# main_V3_0.net
KiCad netlist of a schematic drawn in EAGLE
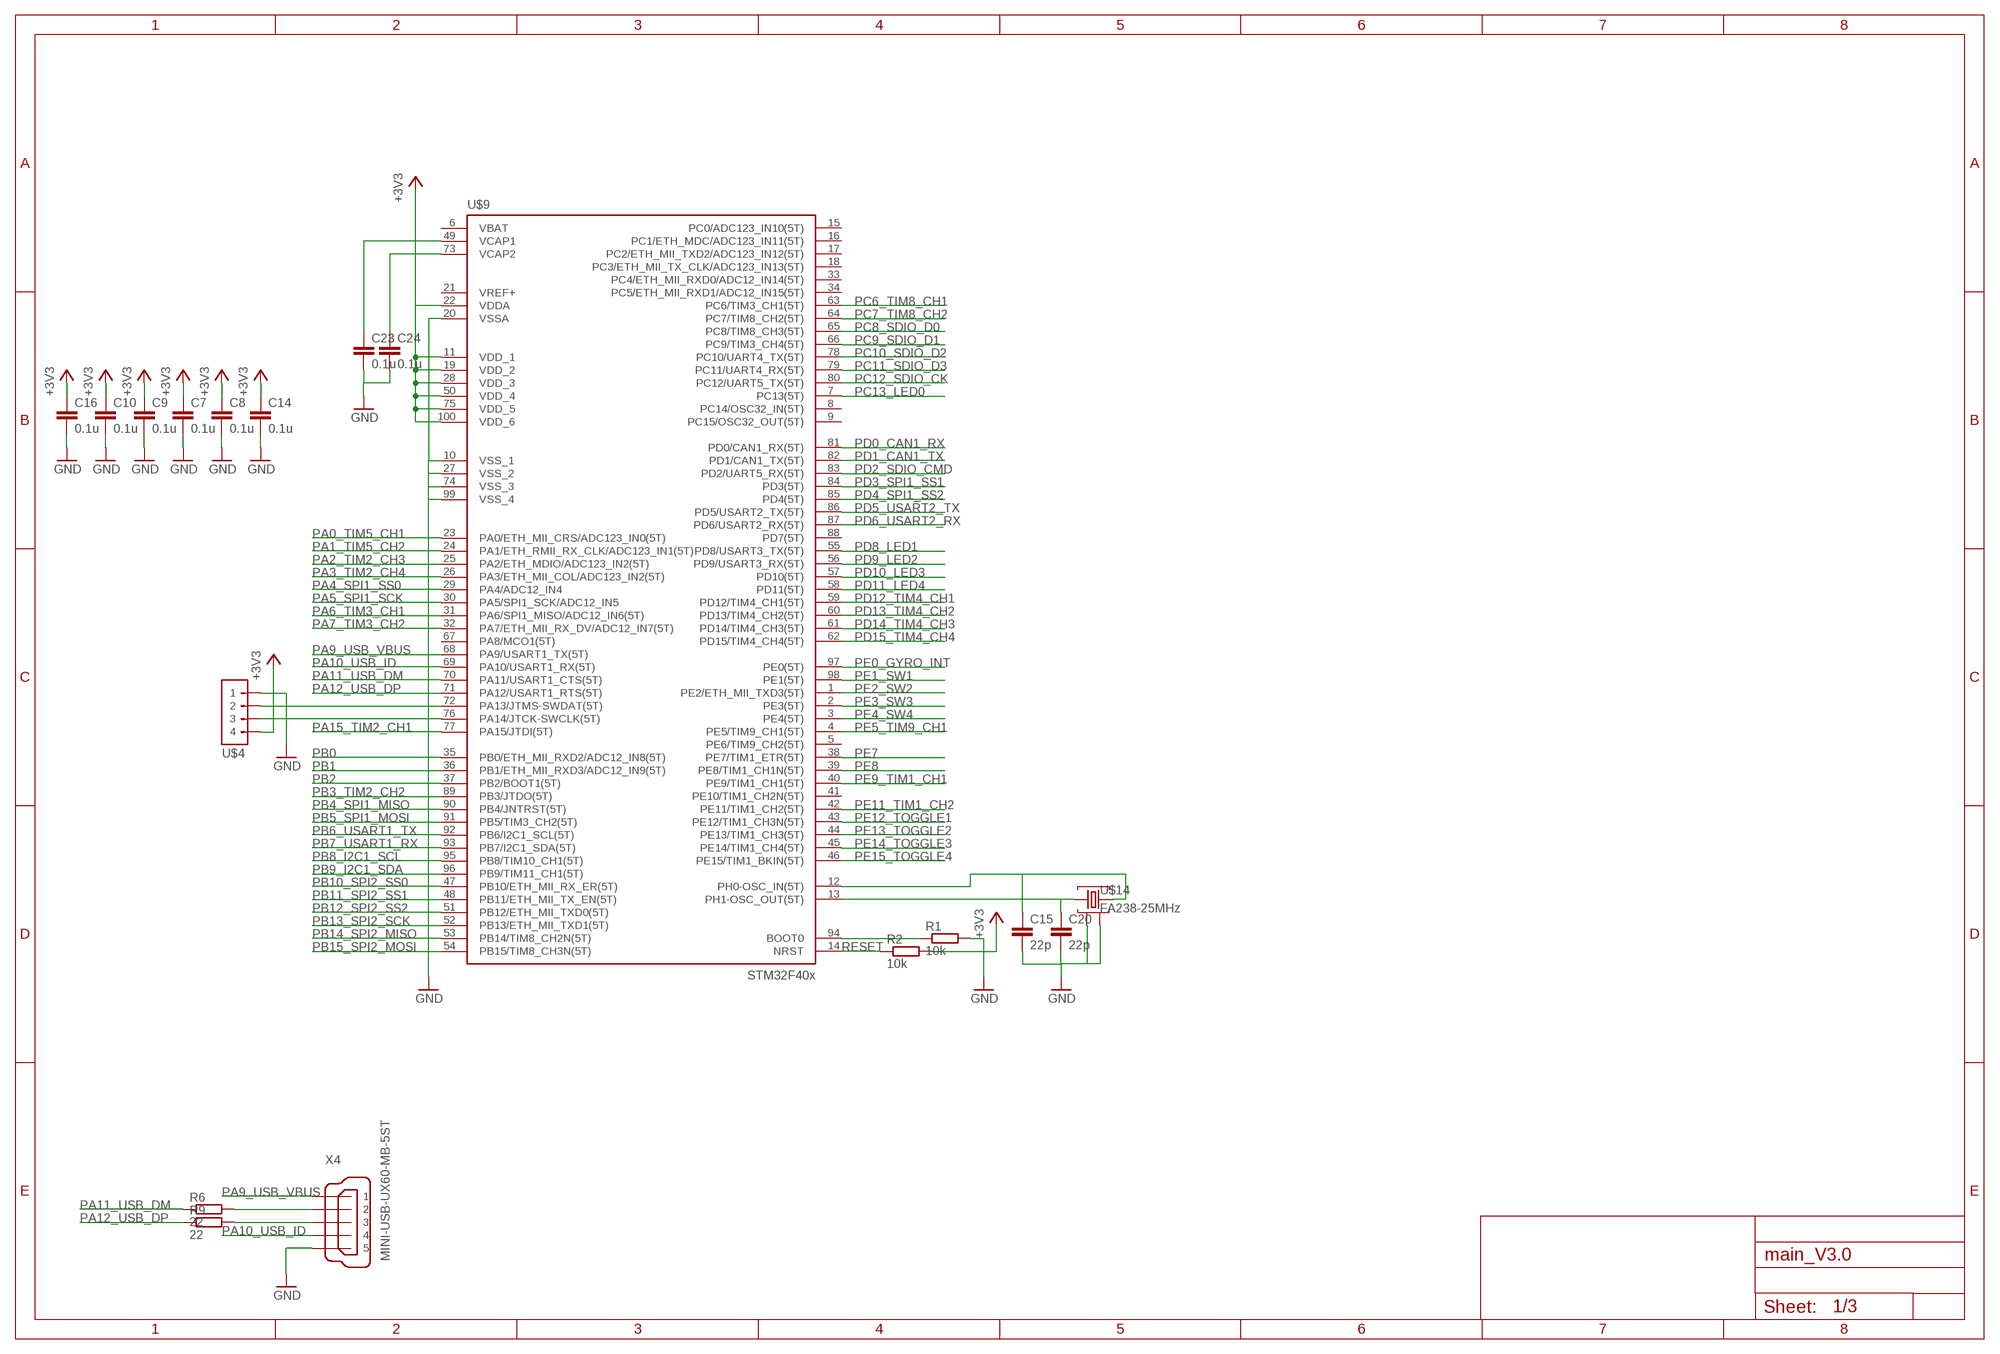
[diagram p0: schematic, sheet 1]
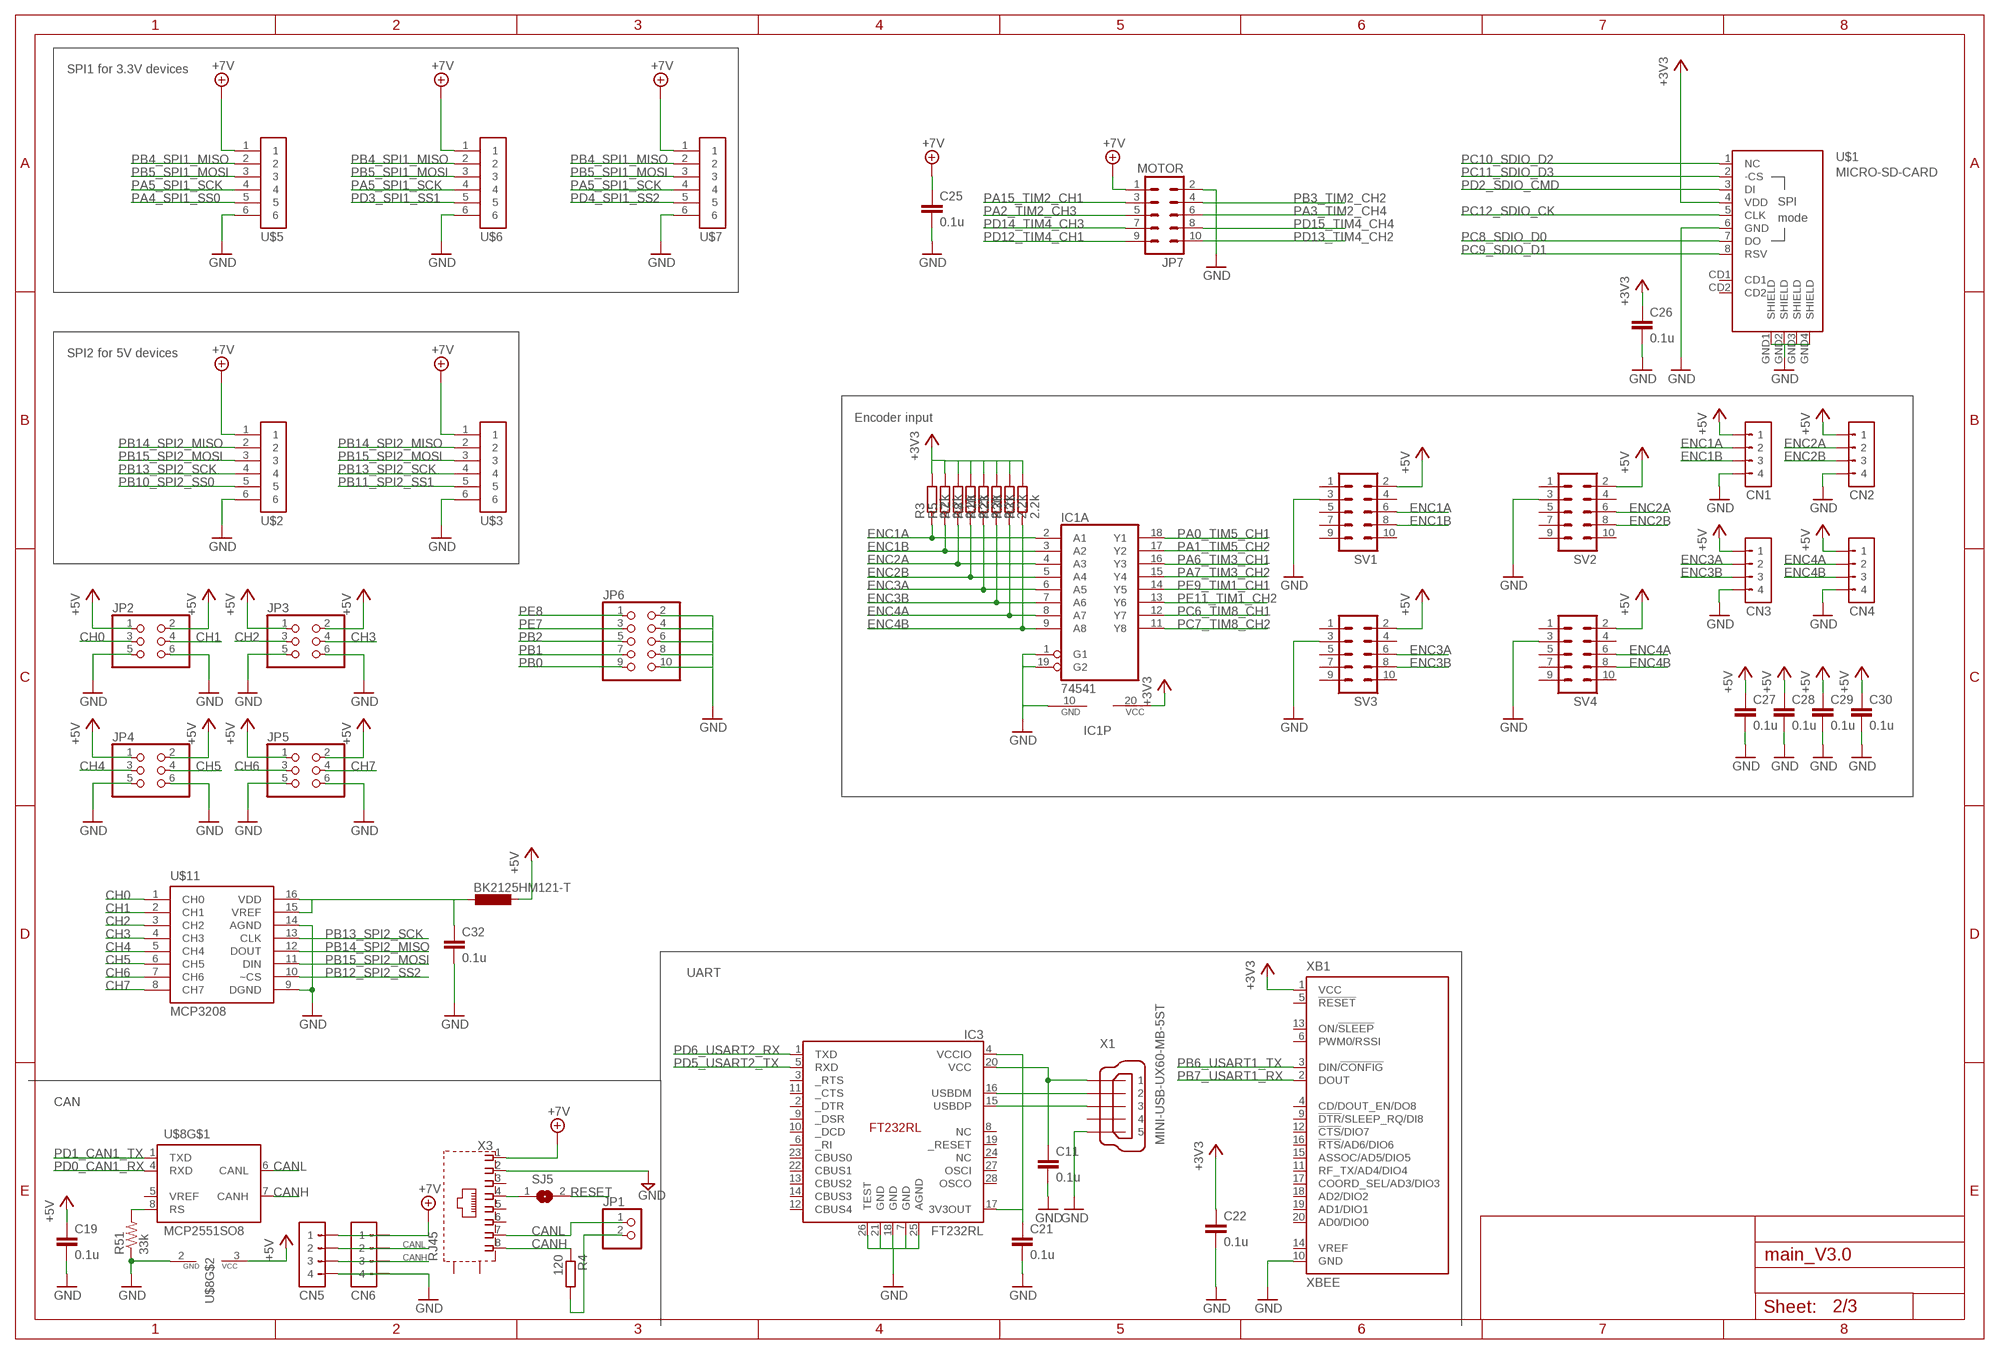
[diagram p1: schematic, sheet 2]
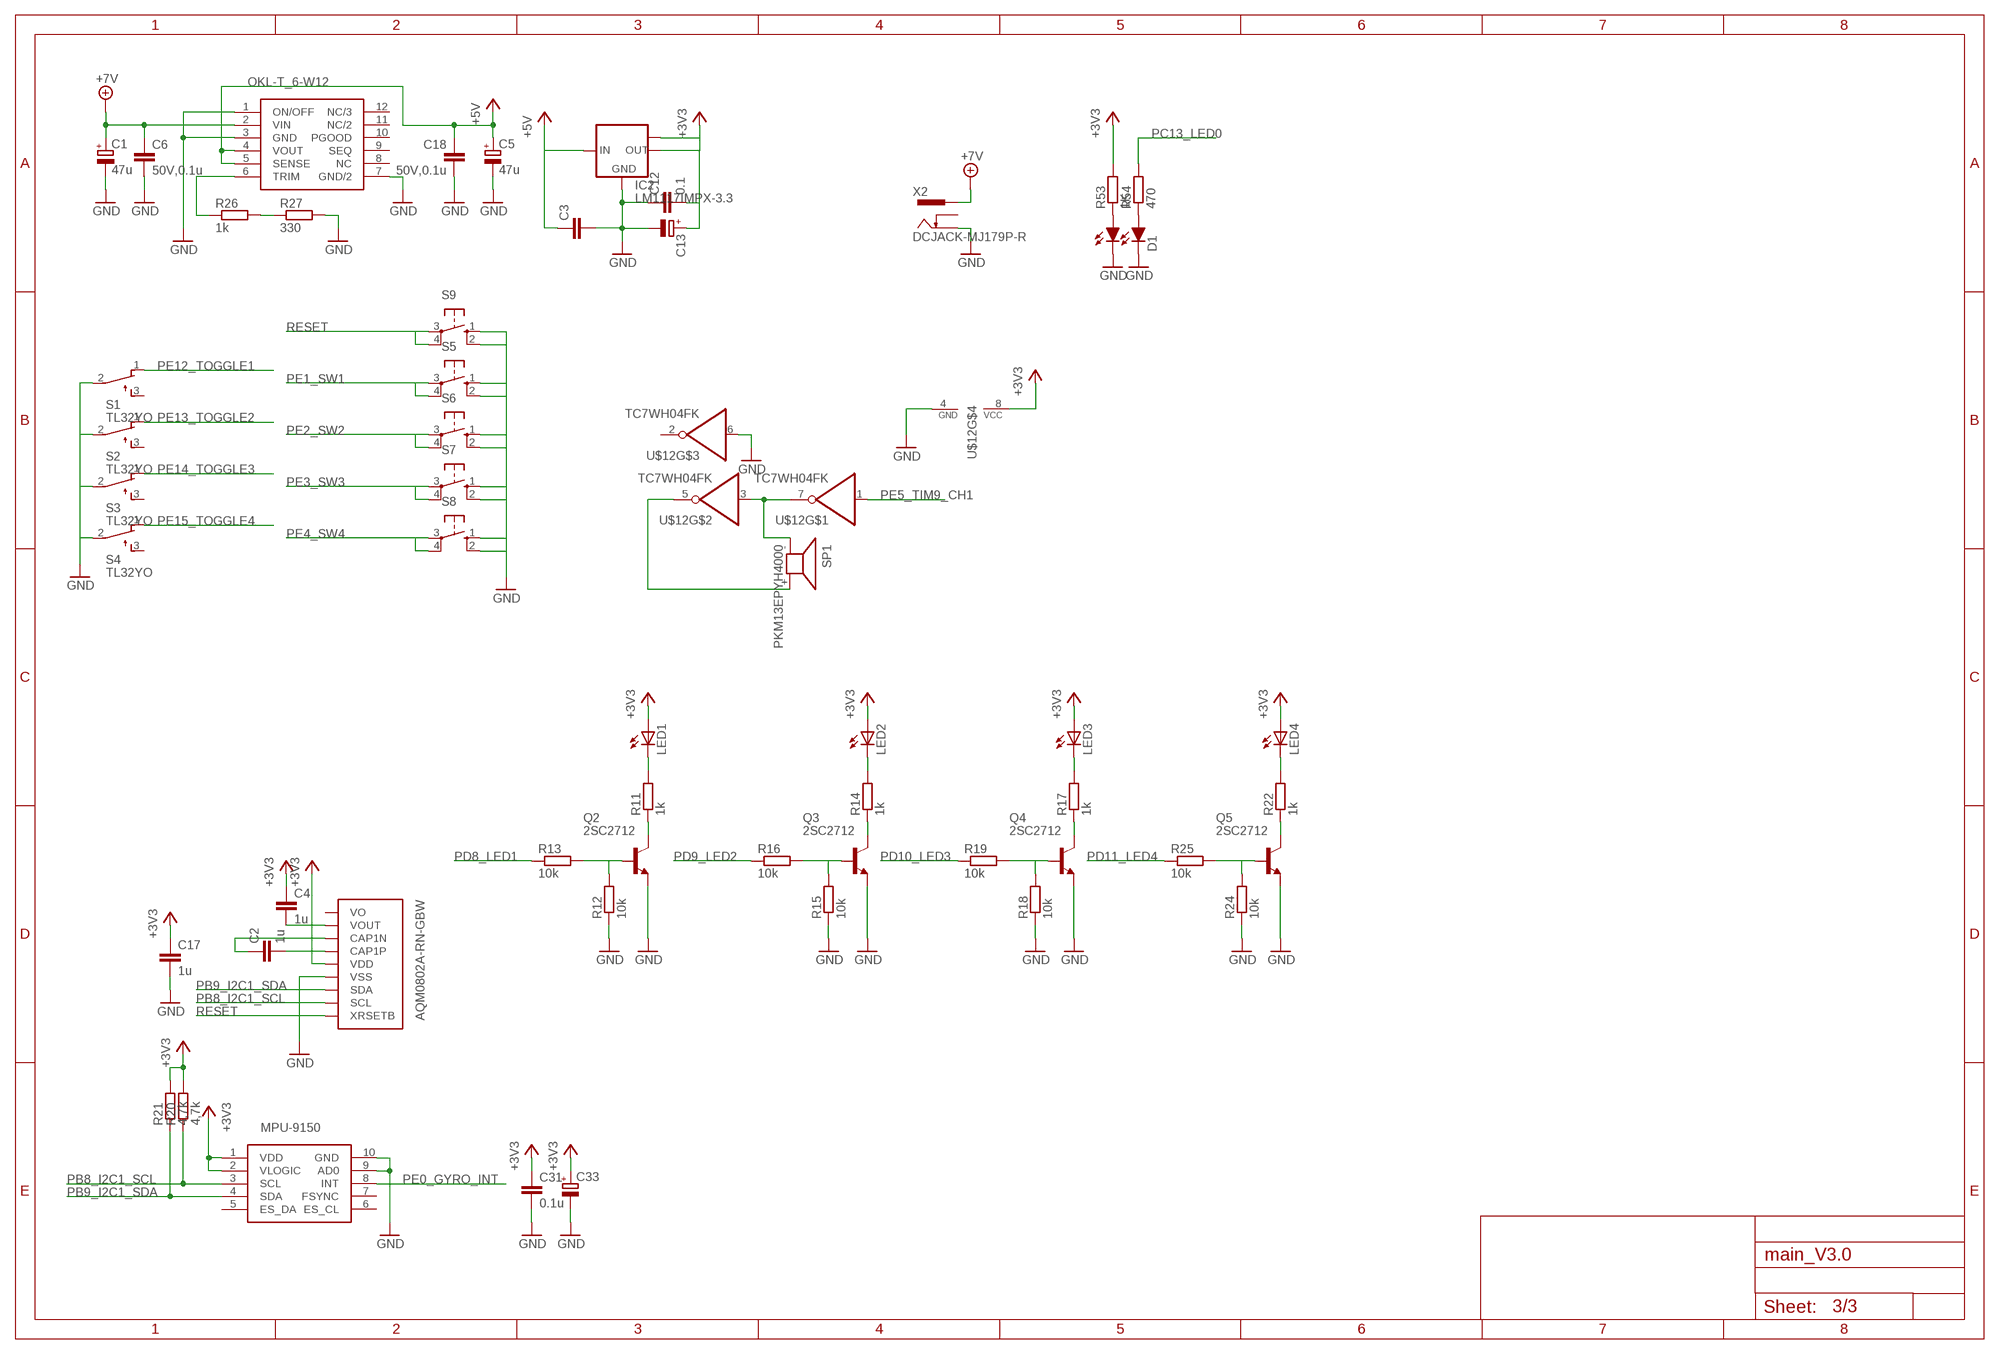
[diagram p2: schematic, sheet 3]

(export (version "E")
  (design (tool "Eeschema 10.0.6"))
  (components
    (comp (ref "AQM0802A-RN-GBW")
      (value "AQM0802A-RN-GBW")
      (footprint "eagle-import:AQM0802")
      (libsource (lib "eagle-import") (part "AQM0802A-RN-GBW"))
    )
    (comp (ref "C1")
      (value "47u")
      (footprint "eagle-import:153CLV-0405")
      (libsource (lib "eagle-import") (part "CPOL-EU153CLV-0405"))
    )
    (comp (ref "C2")
      (value "1u")
      (footprint "eagle-import:C0603K")
      (libsource (lib "eagle-import") (part "C-EUC0603K"))
    )
    (comp (ref "C3")
      (value "C-EUC0603")
      (footprint "eagle-import:C0603")
      (libsource (lib "eagle-import") (part "C-EUC0603"))
    )
    (comp (ref "C4")
      (value "1u")
      (footprint "eagle-import:C0603K")
      (libsource (lib "eagle-import") (part "C-EUC0603K"))
    )
    (comp (ref "C5")
      (value "47u")
      (footprint "eagle-import:153CLV-0405")
      (libsource (lib "eagle-import") (part "CPOL-EU153CLV-0405"))
    )
    (comp (ref "C6")
      (value "50V,0.1u")
      (footprint "eagle-import:C0603K")
      (libsource (lib "eagle-import") (part "C-EUC0603K"))
    )
    (comp (ref "C12")
      (value "0.1")
      (footprint "eagle-import:C0603")
      (libsource (lib "eagle-import") (part "C-EUC0603"))
    )
    (comp (ref "C13")
      (value "CPOL-EU153CLV-0505")
      (footprint "eagle-import:153CLV-0505")
      (libsource (lib "eagle-import") (part "CPOL-EU153CLV-0505"))
    )
    (comp (ref "C17")
      (value "1u")
      (footprint "eagle-import:C0603K")
      (libsource (lib "eagle-import") (part "C-EUC0603K"))
    )
    (comp (ref "C18")
      (value "50V,0.1u")
      (footprint "eagle-import:C0603K")
      (libsource (lib "eagle-import") (part "C-EUC0603K"))
    )
    (comp (ref "C31")
      (value "0.1u")
      (footprint "eagle-import:C0603K")
      (libsource (lib "eagle-import") (part "C-EUC0603K"))
    )
    (comp (ref "C33")
      (value "CPOL-EU153CLV-0505")
      (footprint "eagle-import:153CLV-0505")
      (libsource (lib "eagle-import") (part "CPOL-EU153CLV-0505"))
    )
    (comp (ref "D1")
      (value "SEC2XX4")
      (footprint "eagle-import:LED3025")
      (libsource (lib "eagle-import") (part "SEC2XX4"))
    )
    (comp (ref "IC2")
      (value "LM1117IMPX-3.3")
      (footprint "eagle-import:SOT223")
      (libsource (lib "eagle-import") (part "LM1117IMPX-3.3"))
    )
    (comp (ref "LED1")
      (value "LEDSML0603")
      (footprint "eagle-import:SML0603")
      (libsource (lib "eagle-import") (part "LEDSML0603"))
    )
    (comp (ref "LED2")
      (value "LEDSML0603")
      (footprint "eagle-import:SML0603")
      (libsource (lib "eagle-import") (part "LEDSML0603"))
    )
    (comp (ref "LED3")
      (value "LEDSML0603")
      (footprint "eagle-import:SML0603")
      (libsource (lib "eagle-import") (part "LEDSML0603"))
    )
    (comp (ref "LED4")
      (value "LEDSML0603")
      (footprint "eagle-import:SML0603")
      (libsource (lib "eagle-import") (part "LEDSML0603"))
    )
    (comp (ref "Q2")
      (value "2SC2712")
      (footprint "eagle-import:SC-59(TYPE1)")
      (libsource (lib "eagle-import") (part "2SC2712"))
    )
    (comp (ref "Q3")
      (value "2SC2712")
      (footprint "eagle-import:SC-59(TYPE1)")
      (libsource (lib "eagle-import") (part "2SC2712"))
    )
    (comp (ref "Q4")
      (value "2SC2712")
      (footprint "eagle-import:SC-59(TYPE1)")
      (libsource (lib "eagle-import") (part "2SC2712"))
    )
    (comp (ref "Q5")
      (value "2SC2712")
      (footprint "eagle-import:SC-59(TYPE1)")
      (libsource (lib "eagle-import") (part "2SC2712"))
    )
    (comp (ref "R11")
      (value "1k")
      (footprint "eagle-import:R0603")
      (libsource (lib "eagle-import") (part "R-EU_R0603"))
    )
    (comp (ref "R12")
      (value "10k")
      (footprint "eagle-import:R0603")
      (libsource (lib "eagle-import") (part "R-EU_R0603"))
    )
    (comp (ref "R13")
      (value "10k")
      (footprint "eagle-import:R0603")
      (libsource (lib "eagle-import") (part "R-EU_R0603"))
    )
    (comp (ref "R14")
      (value "1k")
      (footprint "eagle-import:R0603")
      (libsource (lib "eagle-import") (part "R-EU_R0603"))
    )
    (comp (ref "R15")
      (value "10k")
      (footprint "eagle-import:R0603")
      (libsource (lib "eagle-import") (part "R-EU_R0603"))
    )
    (comp (ref "R16")
      (value "10k")
      (footprint "eagle-import:R0603")
      (libsource (lib "eagle-import") (part "R-EU_R0603"))
    )
    (comp (ref "R17")
      (value "1k")
      (footprint "eagle-import:R0603")
      (libsource (lib "eagle-import") (part "R-EU_R0603"))
    )
    (comp (ref "R18")
      (value "10k")
      (footprint "eagle-import:R0603")
      (libsource (lib "eagle-import") (part "R-EU_R0603"))
    )
    (comp (ref "R19")
      (value "10k")
      (footprint "eagle-import:R0603")
      (libsource (lib "eagle-import") (part "R-EU_R0603"))
    )
    (comp (ref "R20")
      (value "4,7k")
      (footprint "eagle-import:R0603")
      (libsource (lib "eagle-import") (part "R-EU_R0603"))
    )
    (comp (ref "R21")
      (value "4,7k")
      (footprint "eagle-import:R0603")
      (libsource (lib "eagle-import") (part "R-EU_R0603"))
    )
    (comp (ref "R22")
      (value "1k")
      (footprint "eagle-import:R0603")
      (libsource (lib "eagle-import") (part "R-EU_R0603"))
    )
    (comp (ref "R24")
      (value "10k")
      (footprint "eagle-import:R0603")
      (libsource (lib "eagle-import") (part "R-EU_R0603"))
    )
    (comp (ref "R25")
      (value "10k")
      (footprint "eagle-import:R0603")
      (libsource (lib "eagle-import") (part "R-EU_R0603"))
    )
    (comp (ref "R26")
      (value "1k")
      (footprint "eagle-import:R0603")
      (libsource (lib "eagle-import") (part "R-EU_R0603"))
    )
    (comp (ref "R27")
      (value "330")
      (footprint "eagle-import:R0603")
      (libsource (lib "eagle-import") (part "R-EU_R0603"))
    )
    (comp (ref "R53")
      (value "1K")
      (footprint "eagle-import:R0603")
      (libsource (lib "eagle-import") (part "R-EU_R0603"))
    )
    (comp (ref "R54")
      (value "470")
      (footprint "eagle-import:R0603")
      (libsource (lib "eagle-import") (part "R-EU_R0603"))
    )
    (comp (ref "S1")
      (value "TL32YO")
      (footprint "eagle-import:TL3XYO")
      (libsource (lib "eagle-import") (part "TL32YO"))
    )
    (comp (ref "S2")
      (value "TL32YO")
      (footprint "eagle-import:TL3XYO")
      (libsource (lib "eagle-import") (part "TL32YO"))
    )
    (comp (ref "S3")
      (value "TL32YO")
      (footprint "eagle-import:TL3XYO")
      (libsource (lib "eagle-import") (part "TL32YO"))
    )
    (comp (ref "S4")
      (value "TL32YO")
      (footprint "eagle-import:TL3XYO")
      (libsource (lib "eagle-import") (part "TL32YO"))
    )
    (comp (ref "S5")
      (value "10-XX")
      (footprint "eagle-import:B3F-10XX")
      (fields (field (name "MPN") "B3F-1000"))
      (libsource (lib "eagle-import") (part "10-XX"))
    )
    (comp (ref "S6")
      (value "10-XX")
      (footprint "eagle-import:B3F-10XX")
      (fields (field (name "MPN") "B3F-1000"))
      (libsource (lib "eagle-import") (part "10-XX"))
    )
    (comp (ref "S7")
      (value "10-XX")
      (footprint "eagle-import:B3F-10XX")
      (fields (field (name "MPN") "B3F-1000"))
      (libsource (lib "eagle-import") (part "10-XX"))
    )
    (comp (ref "S8")
      (value "10-XX")
      (footprint "eagle-import:B3F-10XX")
      (fields (field (name "MPN") "B3F-1000"))
      (libsource (lib "eagle-import") (part "10-XX"))
    )
    (comp (ref "S9")
      (value "10-XX")
      (footprint "eagle-import:B3F-10XX")
      (fields (field (name "MPN") "B3F-1000"))
      (libsource (lib "eagle-import") (part "10-XX"))
    )
    (comp (ref "SP1")
      (value "PKM13EPYH4000")
      (footprint "eagle-import:AL11P")
      (libsource (lib "eagle-import") (part "AL11P"))
    )
    (comp (ref "U$10")
      (value "MPU-9150")
      (footprint "eagle-import:MPU-9150")
      (libsource (lib "eagle-import") (part "MPU-9150"))
    )
    (comp (ref "U$12")
      (value "TC7WH04FK")
      (footprint "eagle-import:SSOP08")
      (libsource (lib "eagle-import") (part "TC7WH04FK"))
    )
    (comp (ref "U$13")
      (value "OKL-T/6-W12N")
      (footprint "eagle-import:OKL-T_6-W12")
      (libsource (lib "eagle-import") (part "OKL-T/6-W12N"))
    )
    (comp (ref "X2")
      (value "DCJACK-MJ179P-R")
      (footprint "eagle-import:MJ-179P-R")
      (libsource (lib "eagle-import") (part "DCJACK-MJ179P-R"))
    )
    (comp (ref "BK2125HM121-T")
      (value "L-EUL2012C")
      (footprint "eagle-import:L2012C")
      (libsource (lib "eagle-import") (part "L-EUL2012C"))
    )
    (comp (ref "C11")
      (value "0.1u")
      (footprint "eagle-import:C0603K")
      (libsource (lib "eagle-import") (part "C-EUC0603K"))
    )
    (comp (ref "C19")
      (value "0.1u")
      (footprint "eagle-import:C0603K")
      (libsource (lib "eagle-import") (part "C-EUC0603K"))
    )
    (comp (ref "C21")
      (value "0.1u")
      (footprint "eagle-import:C0603K")
      (libsource (lib "eagle-import") (part "C-EUC0603K"))
    )
    (comp (ref "C22")
      (value "0.1u")
      (footprint "eagle-import:C0603K")
      (libsource (lib "eagle-import") (part "C-EUC0603K"))
    )
    (comp (ref "C25")
      (value "0.1u")
      (footprint "eagle-import:C0603K")
      (libsource (lib "eagle-import") (part "C-EUC0603K"))
    )
    (comp (ref "C26")
      (value "0.1u")
      (footprint "eagle-import:C0603K")
      (libsource (lib "eagle-import") (part "C-EUC0603K"))
    )
    (comp (ref "C27")
      (value "0.1u")
      (footprint "eagle-import:C0603K")
      (libsource (lib "eagle-import") (part "C-EUC0603K"))
    )
    (comp (ref "C28")
      (value "0.1u")
      (footprint "eagle-import:C0603K")
      (libsource (lib "eagle-import") (part "C-EUC0603K"))
    )
    (comp (ref "C29")
      (value "0.1u")
      (footprint "eagle-import:C0603K")
      (libsource (lib "eagle-import") (part "C-EUC0603K"))
    )
    (comp (ref "C30")
      (value "0.1u")
      (footprint "eagle-import:C0603K")
      (libsource (lib "eagle-import") (part "C-EUC0603K"))
    )
    (comp (ref "C32")
      (value "0.1u")
      (footprint "eagle-import:C0603K")
      (libsource (lib "eagle-import") (part "C-EUC0603K"))
    )
    (comp (ref "CN1")
      (value "CN4-JST-XH-TOP")
      (footprint "eagle-import:JST-B4B-XH-A")
      (libsource (lib "eagle-import") (part "CN4-JST-XH-TOP"))
    )
    (comp (ref "CN2")
      (value "CN4-JST-XH-TOP")
      (footprint "eagle-import:JST-B4B-XH-A")
      (libsource (lib "eagle-import") (part "CN4-JST-XH-TOP"))
    )
    (comp (ref "CN3")
      (value "CN4-JST-XH-TOP")
      (footprint "eagle-import:JST-B4B-XH-A")
      (libsource (lib "eagle-import") (part "CN4-JST-XH-TOP"))
    )
    (comp (ref "CN4")
      (value "CN4-JST-XH-TOP")
      (footprint "eagle-import:JST-B4B-XH-A")
      (libsource (lib "eagle-import") (part "CN4-JST-XH-TOP"))
    )
    (comp (ref "CN5")
      (value "CN4-JST-XH-TOP")
      (footprint "eagle-import:JST-B4B-XH-A")
      (libsource (lib "eagle-import") (part "CN4-JST-XH-TOP"))
    )
    (comp (ref "CN6")
      (value "CN4-JST-XH-TOP")
      (footprint "eagle-import:JST-B4B-XH-A")
      (libsource (lib "eagle-import") (part "CN4-JST-XH-TOP"))
    )
    (comp (ref "IC1")
      (value "74541")
      (footprint "eagle-import:SOP20")
      (libsource (lib "eagle-import") (part "74541"))
    )
    (comp (ref "IC3")
      (value "FT232RL")
      (footprint "eagle-import:SSOP-28")
      (libsource (lib "eagle-import") (part "FT232RL"))
    )
    (comp (ref "JP1")
      (value "PINHD-1X2")
      (footprint "eagle-import:1X02")
      (libsource (lib "eagle-import") (part "PINHD-1X2"))
    )
    (comp (ref "JP2")
      (value "PINHD-2X3/90")
      (footprint "eagle-import:2X03_90")
      (libsource (lib "eagle-import") (part "PINHD-2X3/90"))
    )
    (comp (ref "JP3")
      (value "PINHD-2X3/90")
      (footprint "eagle-import:2X03_90")
      (libsource (lib "eagle-import") (part "PINHD-2X3/90"))
    )
    (comp (ref "JP4")
      (value "PINHD-2X3/90")
      (footprint "eagle-import:2X03_90")
      (libsource (lib "eagle-import") (part "PINHD-2X3/90"))
    )
    (comp (ref "JP5")
      (value "PINHD-2X3/90")
      (footprint "eagle-import:2X03_90")
      (libsource (lib "eagle-import") (part "PINHD-2X3/90"))
    )
    (comp (ref "JP6")
      (value "PINHD-2X5/90")
      (footprint "eagle-import:2X05_90")
      (libsource (lib "eagle-import") (part "PINHD-2X5/90"))
    )
    (comp (ref "JP7")
      (value "MOTOR")
      (footprint "eagle-import:ML10L")
      (libsource (lib "eagle-import") (part "ML10L"))
    )
    (comp (ref "R3")
      (value "2.2k")
      (footprint "eagle-import:R0603")
      (libsource (lib "eagle-import") (part "R-EU_R0603"))
    )
    (comp (ref "R4")
      (value "120")
      (footprint "eagle-import:R0603")
      (libsource (lib "eagle-import") (part "R-EU_R0603"))
    )
    (comp (ref "R5")
      (value "2.2k")
      (footprint "eagle-import:R0603")
      (libsource (lib "eagle-import") (part "R-EU_R0603"))
    )
    (comp (ref "R7")
      (value "2.2k")
      (footprint "eagle-import:R0603")
      (libsource (lib "eagle-import") (part "R-EU_R0603"))
    )
    (comp (ref "R8")
      (value "2.2k")
      (footprint "eagle-import:R0603")
      (libsource (lib "eagle-import") (part "R-EU_R0603"))
    )
    (comp (ref "R10")
      (value "2.2k")
      (footprint "eagle-import:R0603")
      (libsource (lib "eagle-import") (part "R-EU_R0603"))
    )
    (comp (ref "R23")
      (value "2.2k")
      (footprint "eagle-import:R0603")
      (libsource (lib "eagle-import") (part "R-EU_R0603"))
    )
    (comp (ref "R30")
      (value "2.2k")
      (footprint "eagle-import:R0603")
      (libsource (lib "eagle-import") (part "R-EU_R0603"))
    )
    (comp (ref "R31")
      (value "2.2k")
      (footprint "eagle-import:R0603")
      (libsource (lib "eagle-import") (part "R-EU_R0603"))
    )
    (comp (ref "R51")
      (value "33k")
      (footprint "eagle-import:R0603")
      (libsource (lib "eagle-import") (part "R-US_R0603"))
    )
    (comp (ref "SJ5") (value "SJ") (footprint "eagle-import:SJ") (libsource (lib "eagle-import") (part "SJ")))
    (comp (ref "SV1")
      (value "ML10L")
      (footprint "eagle-import:ML10L")
      (libsource (lib "eagle-import") (part "con-ml_ML10L"))
    )
    (comp (ref "SV2")
      (value "ML10L")
      (footprint "eagle-import:ML10L")
      (libsource (lib "eagle-import") (part "con-ml_ML10L"))
    )
    (comp (ref "SV3")
      (value "ML10L")
      (footprint "eagle-import:ML10L")
      (libsource (lib "eagle-import") (part "con-ml_ML10L"))
    )
    (comp (ref "SV4")
      (value "ML10L")
      (footprint "eagle-import:ML10L")
      (libsource (lib "eagle-import") (part "con-ml_ML10L"))
    )
    (comp (ref "U$1")
      (value "MICRO-SD-CARD")
      (footprint "eagle-import:DM3AT-SF-PEJ")
      (libsource (lib "eagle-import") (part "MICRO-SD-CARD"))
    )
    (comp (ref "U$2")
      (value "CN6")
      (footprint "eagle-import:JST-B6B-XH-A")
      (libsource (lib "eagle-import") (part "CN6"))
    )
    (comp (ref "U$3")
      (value "CN6")
      (footprint "eagle-import:JST-B6B-XH-A")
      (libsource (lib "eagle-import") (part "CN6"))
    )
    (comp (ref "U$5")
      (value "CN6")
      (footprint "eagle-import:JST-B6B-XH-A")
      (libsource (lib "eagle-import") (part "CN6"))
    )
    (comp (ref "U$6")
      (value "CN6")
      (footprint "eagle-import:JST-B6B-XH-A")
      (libsource (lib "eagle-import") (part "CN6"))
    )
    (comp (ref "U$7")
      (value "CN6")
      (footprint "eagle-import:JST-B6B-XH-A")
      (libsource (lib "eagle-import") (part "CN6"))
    )
    (comp (ref "U$8")
      (value "MCP2551SO8")
      (footprint "eagle-import:SO08")
      (libsource (lib "eagle-import") (part "MCP2551SO8"))
    )
    (comp (ref "U$11")
      (value "MCP3208")
      (footprint "eagle-import:SO16")
      (libsource (lib "eagle-import") (part "MCP3208"))
    )
    (comp (ref "X1")
      (value "MINI-USB-UX60-MB-5ST")
      (footprint "eagle-import:UX60-MB-5ST")
      (libsource (lib "eagle-import") (part "MINI-USB-UX60-MB-5ST"))
    )
    (comp (ref "X3")
      (value "RJ45")
      (footprint "eagle-import:LAN")
      (libsource (lib "eagle-import") (part "RJ45"))
    )
    (comp (ref "XB1")
      (value "XBEE")
      (footprint "eagle-import:XBEE")
      (libsource (lib "eagle-import") (part "XBEE"))
    )
    (comp (ref "C7")
      (value "0.1u")
      (footprint "eagle-import:C0603K")
      (libsource (lib "eagle-import") (part "C-EUC0603K"))
    )
    (comp (ref "C8")
      (value "0.1u")
      (footprint "eagle-import:C0603K")
      (libsource (lib "eagle-import") (part "C-EUC0603K"))
    )
    (comp (ref "C9")
      (value "0.1u")
      (footprint "eagle-import:C0603K")
      (libsource (lib "eagle-import") (part "C-EUC0603K"))
    )
    (comp (ref "C10")
      (value "0.1u")
      (footprint "eagle-import:C0603K")
      (libsource (lib "eagle-import") (part "C-EUC0603K"))
    )
    (comp (ref "C14")
      (value "0.1u")
      (footprint "eagle-import:C0603K")
      (libsource (lib "eagle-import") (part "C-EUC0603K"))
    )
    (comp (ref "C15")
      (value "22p")
      (footprint "eagle-import:C0603K")
      (libsource (lib "eagle-import") (part "C-EUC0603K"))
    )
    (comp (ref "C16")
      (value "0.1u")
      (footprint "eagle-import:C0603K")
      (libsource (lib "eagle-import") (part "C-EUC0603K"))
    )
    (comp (ref "C20")
      (value "22p")
      (footprint "eagle-import:C0603K")
      (libsource (lib "eagle-import") (part "C-EUC0603K"))
    )
    (comp (ref "C23")
      (value "0.1u")
      (footprint "eagle-import:C0603K")
      (libsource (lib "eagle-import") (part "C-EUC0603K"))
    )
    (comp (ref "C24")
      (value "0.1u")
      (footprint "eagle-import:C0603K")
      (libsource (lib "eagle-import") (part "C-EUC0603K"))
    )
    (comp (ref "R1")
      (value "10k")
      (footprint "eagle-import:R0603")
      (libsource (lib "eagle-import") (part "R-EU_R0603"))
    )
    (comp (ref "R2")
      (value "10k")
      (footprint "eagle-import:R0603")
      (libsource (lib "eagle-import") (part "R-EU_R0603"))
    )
    (comp (ref "R6")
      (value "22")
      (footprint "eagle-import:R0603")
      (libsource (lib "eagle-import") (part "R-EU_R0603"))
    )
    (comp (ref "R9")
      (value "22")
      (footprint "eagle-import:R0603")
      (libsource (lib "eagle-import") (part "R-EU_R0603"))
    )
    (comp (ref "U$4")
      (value "TOP_TYPE_4PIN")
      (footprint "eagle-import:TOP_TYPE_4PIN")
      (libsource (lib "eagle-import") (part "TOP_TYPE_4PIN"))
    )
    (comp (ref "U$9")
      (value "STM32F407V")
      (footprint "eagle-import:TQFP100")
      (libsource (lib "eagle-import") (part "STM32F407V"))
    )
    (comp (ref "U$14")
      (value "FA238-25MHz")
      (footprint "eagle-import:ASF")
      (libsource (lib "eagle-import") (part "FA238"))
    )
    (comp (ref "X4")
      (value "MINI-USB-UX60-MB-5ST")
      (footprint "eagle-import:UX60-MB-5ST")
      (libsource (lib "eagle-import") (part "MINI-USB-UX60-MB-5ST"))
    )
  )
  (nets
    (net (code "1") (name "+3V3") (class "Default")
      (node (ref "AQM0802A-RN-GBW") (pin "P$5") (pinfunction "VDD_P$5") (pintype "bidirectional"))
      (node (ref "C10") (pin "1") (pinfunction "1_1") (pintype "passive"))
      (node (ref "C12") (pin "2") (pinfunction "2_2") (pintype "passive"))
      (node (ref "C13") (pin "+") (pinfunction "+_+") (pintype "passive"))
      (node (ref "C14") (pin "1") (pinfunction "1_1") (pintype "passive"))
      (node (ref "C16") (pin "1") (pinfunction "1_1") (pintype "passive"))
      (node (ref "C17") (pin "1") (pinfunction "1_1") (pintype "passive"))
      (node (ref "C22") (pin "1") (pinfunction "1_1") (pintype "passive"))
      (node (ref "C26") (pin "1") (pinfunction "1_1") (pintype "passive"))
      (node (ref "C31") (pin "1") (pinfunction "1_1") (pintype "passive"))
      (node (ref "C33") (pin "+") (pinfunction "+_+") (pintype "passive"))
      (node (ref "C4") (pin "1") (pinfunction "1_1") (pintype "passive"))
      (node (ref "C7") (pin "1") (pinfunction "1_1") (pintype "passive"))
      (node (ref "C8") (pin "1") (pinfunction "1_1") (pintype "passive"))
      (node (ref "C9") (pin "1") (pinfunction "1_1") (pintype "passive"))
      (node (ref "IC1") (pin "20") (pinfunction "VCC_20") (pintype "power_in"))
      (node (ref "IC2") (pin "2") (pinfunction "OUT_2") (pintype "passive"))
      (node (ref "IC2") (pin "TAB") (pinfunction "OUT1_TAB") (pintype "passive"))
      (node (ref "LED1") (pin "A") (pinfunction "A_A") (pintype "passive"))
      (node (ref "LED2") (pin "A") (pinfunction "A_A") (pintype "passive"))
      (node (ref "LED3") (pin "A") (pinfunction "A_A") (pintype "passive"))
      (node (ref "LED4") (pin "A") (pinfunction "A_A") (pintype "passive"))
      (node (ref "R10") (pin "2") (pinfunction "2_2") (pintype "passive"))
      (node (ref "R2") (pin "2") (pinfunction "2_2") (pintype "passive"))
      (node (ref "R20") (pin "2") (pinfunction "2_2") (pintype "passive"))
      (node (ref "R21") (pin "2") (pinfunction "2_2") (pintype "passive"))
      (node (ref "R23") (pin "2") (pinfunction "2_2") (pintype "passive"))
      (node (ref "R3") (pin "2") (pinfunction "2_2") (pintype "passive"))
      (node (ref "R30") (pin "2") (pinfunction "2_2") (pintype "passive"))
      (node (ref "R31") (pin "2") (pinfunction "2_2") (pintype "passive"))
      (node (ref "R5") (pin "2") (pinfunction "2_2") (pintype "passive"))
      (node (ref "R53") (pin "2") (pinfunction "2_2") (pintype "passive"))
      (node (ref "R7") (pin "2") (pinfunction "2_2") (pintype "passive"))
      (node (ref "R8") (pin "2") (pinfunction "2_2") (pintype "passive"))
      (node (ref "U$1") (pin "4") (pinfunction "VDD_4") (pintype "bidirectional"))
      (node (ref "U$10") (pin "1") (pinfunction "VDD_1") (pintype "bidirectional"))
      (node (ref "U$10") (pin "2") (pinfunction "VLOGIC_2") (pintype "bidirectional"))
      (node (ref "U$12") (pin "8") (pinfunction "VCC_8") (pintype "power_in"))
      (node (ref "U$4") (pin "4") (pinfunction "4_4") (pintype "passive"))
      (node (ref "U$9") (pin "100") (pinfunction "VDD_6_100") (pintype "bidirectional"))
      (node (ref "U$9") (pin "11") (pinfunction "VDD_1_11") (pintype "bidirectional"))
      (node (ref "U$9") (pin "19") (pinfunction "VDD_2_19") (pintype "bidirectional"))
      (node (ref "U$9") (pin "22") (pinfunction "VDDA_22") (pintype "bidirectional"))
      (node (ref "U$9") (pin "28") (pinfunction "VDD_3_28") (pintype "bidirectional"))
      (node (ref "U$9") (pin "50") (pinfunction "VDD_4_50") (pintype "bidirectional"))
      (node (ref "U$9") (pin "75") (pinfunction "VDD_5_75") (pintype "bidirectional"))
      (node (ref "XB1") (pin "1") (pinfunction "VCC_1") (pintype "power_in"))
    )
    (net (code "2") (name "+5V") (class "Default")
      (node (ref "BK2125HM121-T") (pin "1") (pinfunction "1_1") (pintype "passive"))
      (node (ref "C18") (pin "1") (pinfunction "1_1") (pintype "passive"))
      (node (ref "C19") (pin "1") (pinfunction "1_1") (pintype "passive"))
      (node (ref "C27") (pin "1") (pinfunction "1_1") (pintype "passive"))
      (node (ref "C28") (pin "1") (pinfunction "1_1") (pintype "passive"))
      (node (ref "C29") (pin "1") (pinfunction "1_1") (pintype "passive"))
      (node (ref "C3") (pin "1") (pinfunction "1_1") (pintype "passive"))
      (node (ref "C30") (pin "1") (pinfunction "1_1") (pintype "passive"))
      (node (ref "C5") (pin "+") (pinfunction "+_+") (pintype "passive"))
      (node (ref "CN1") (pin "1") (pinfunction "1_1") (pintype "passive"))
      (node (ref "CN2") (pin "1") (pinfunction "1_1") (pintype "passive"))
      (node (ref "CN3") (pin "1") (pinfunction "1_1") (pintype "passive"))
      (node (ref "CN4") (pin "1") (pinfunction "1_1") (pintype "passive"))
      (node (ref "IC2") (pin "3") (pinfunction "IN_3") (pintype "input"))
      (node (ref "JP2") (pin "1") (pinfunction "1_1") (pintype "passive"))
      (node (ref "JP2") (pin "2") (pinfunction "2_2") (pintype "passive"))
      (node (ref "JP3") (pin "1") (pinfunction "1_1") (pintype "passive"))
      (node (ref "JP3") (pin "2") (pinfunction "2_2") (pintype "passive"))
      (node (ref "JP4") (pin "1") (pinfunction "1_1") (pintype "passive"))
      (node (ref "JP4") (pin "2") (pinfunction "2_2") (pintype "passive"))
      (node (ref "JP5") (pin "1") (pinfunction "1_1") (pintype "passive"))
      (node (ref "JP5") (pin "2") (pinfunction "2_2") (pintype "passive"))
      (node (ref "SV1") (pin "2") (pinfunction "2_2") (pintype "passive"))
      (node (ref "SV2") (pin "2") (pinfunction "2_2") (pintype "passive"))
      (node (ref "SV3") (pin "2") (pinfunction "2_2") (pintype "passive"))
      (node (ref "SV4") (pin "2") (pinfunction "2_2") (pintype "passive"))
      (node (ref "U$13") (pin "4") (pinfunction "VOUT_4") (pintype "bidirectional"))
      (node (ref "U$13") (pin "5") (pinfunction "SENSE_5") (pintype "bidirectional"))
      (node (ref "U$8") (pin "3") (pinfunction "VCC_3") (pintype "power_in"))
    )
    (net (code "3") (name "+7V") (class "Default")
      (node (ref "C1") (pin "+") (pinfunction "+_+") (pintype "passive"))
      (node (ref "C25") (pin "1") (pinfunction "1_1") (pintype "passive"))
      (node (ref "C6") (pin "1") (pinfunction "1_1") (pintype "passive"))
      (node (ref "CN5") (pin "1") (pinfunction "1_1") (pintype "passive"))
      (node (ref "CN6") (pin "1") (pinfunction "1_1") (pintype "passive"))
      (node (ref "JP7") (pin "1") (pinfunction "1_1") (pintype "passive"))
      (node (ref "U$13") (pin "2") (pinfunction "VIN_2") (pintype "bidirectional"))
      (node (ref "U$2") (pin "1") (pinfunction "1_1") (pintype "passive"))
      (node (ref "U$3") (pin "1") (pinfunction "1_1") (pintype "passive"))
      (node (ref "U$5") (pin "1") (pinfunction "1_1") (pintype "passive"))
      (node (ref "U$6") (pin "1") (pinfunction "1_1") (pintype "passive"))
      (node (ref "U$7") (pin "1") (pinfunction "1_1") (pintype "passive"))
      (node (ref "X2") (pin "1") (pinfunction "1_1") (pintype "passive"))
      (node (ref "X3") (pin "1") (pinfunction "1_1") (pintype "passive"))
    )
    (net (code "4") (name "CANH") (class "Default")
      (node (ref "CN5") (pin "3") (pinfunction "3_3") (pintype "passive"))
      (node (ref "CN6") (pin "3") (pinfunction "3_3") (pintype "passive"))
      (node (ref "R4") (pin "1") (pinfunction "1_1") (pintype "passive"))
      (node (ref "U$8") (pin "7") (pinfunction "CANH_7") (pintype "bidirectional"))
      (node (ref "X3") (pin "8") (pinfunction "8_8") (pintype "passive"))
    )
    (net (code "5") (name "CANL") (class "Default")
      (node (ref "CN5") (pin "2") (pinfunction "2_2") (pintype "passive"))
      (node (ref "CN6") (pin "2") (pinfunction "2_2") (pintype "passive"))
      (node (ref "JP1") (pin "1") (pinfunction "1_1") (pintype "passive"))
      (node (ref "U$8") (pin "6") (pinfunction "CANL_6") (pintype "bidirectional"))
      (node (ref "X3") (pin "7") (pinfunction "7_7") (pintype "passive"))
    )
    (net (code "6") (name "CH0") (class "Default")
      (node (ref "JP2") (pin "3") (pinfunction "3_3") (pintype "passive"))
      (node (ref "U$11") (pin "1") (pinfunction "CH0_1") (pintype "bidirectional"))
    )
    (net (code "7") (name "CH1") (class "Default")
      (node (ref "JP2") (pin "4") (pinfunction "4_4") (pintype "passive"))
      (node (ref "U$11") (pin "2") (pinfunction "CH1_2") (pintype "bidirectional"))
    )
    (net (code "8") (name "CH2") (class "Default")
      (node (ref "JP3") (pin "3") (pinfunction "3_3") (pintype "passive"))
      (node (ref "U$11") (pin "3") (pinfunction "CH2_3") (pintype "bidirectional"))
    )
    (net (code "9") (name "CH3") (class "Default")
      (node (ref "JP3") (pin "4") (pinfunction "4_4") (pintype "passive"))
      (node (ref "U$11") (pin "4") (pinfunction "CH3_4") (pintype "bidirectional"))
    )
    (net (code "10") (name "CH4") (class "Default")
      (node (ref "JP4") (pin "3") (pinfunction "3_3") (pintype "passive"))
      (node (ref "U$11") (pin "5") (pinfunction "CH4_5") (pintype "bidirectional"))
    )
    (net (code "11") (name "CH5") (class "Default")
      (node (ref "JP4") (pin "4") (pinfunction "4_4") (pintype "passive"))
      (node (ref "U$11") (pin "6") (pinfunction "CH5_6") (pintype "bidirectional"))
    )
    (net (code "12") (name "CH6") (class "Default")
      (node (ref "JP5") (pin "3") (pinfunction "3_3") (pintype "passive"))
      (node (ref "U$11") (pin "7") (pinfunction "CH6_7") (pintype "bidirectional"))
    )
    (net (code "13") (name "CH7") (class "Default")
      (node (ref "JP5") (pin "4") (pinfunction "4_4") (pintype "passive"))
      (node (ref "U$11") (pin "8") (pinfunction "CH7_8") (pintype "bidirectional"))
    )
    (net (code "14") (name "ENC1A") (class "Default")
      (node (ref "CN1") (pin "2") (pinfunction "2_2") (pintype "passive"))
      (node (ref "IC1") (pin "2") (pinfunction "A1_2") (pintype "input"))
      (node (ref "R3") (pin "1") (pinfunction "1_1") (pintype "passive"))
      (node (ref "SV1") (pin "6") (pinfunction "6_6") (pintype "passive"))
    )
    (net (code "15") (name "ENC1B") (class "Default")
      (node (ref "CN1") (pin "3") (pinfunction "3_3") (pintype "passive"))
      (node (ref "IC1") (pin "3") (pinfunction "A2_3") (pintype "input"))
      (node (ref "R5") (pin "1") (pinfunction "1_1") (pintype "passive"))
      (node (ref "SV1") (pin "8") (pinfunction "8_8") (pintype "passive"))
    )
    (net (code "16") (name "ENC2A") (class "Default")
      (node (ref "CN2") (pin "2") (pinfunction "2_2") (pintype "passive"))
      (node (ref "IC1") (pin "4") (pinfunction "A3_4") (pintype "input"))
      (node (ref "R7") (pin "1") (pinfunction "1_1") (pintype "passive"))
      (node (ref "SV2") (pin "6") (pinfunction "6_6") (pintype "passive"))
    )
    (net (code "17") (name "ENC2B") (class "Default")
      (node (ref "CN2") (pin "3") (pinfunction "3_3") (pintype "passive"))
      (node (ref "IC1") (pin "5") (pinfunction "A4_5") (pintype "input"))
      (node (ref "R8") (pin "1") (pinfunction "1_1") (pintype "passive"))
      (node (ref "SV2") (pin "8") (pinfunction "8_8") (pintype "passive"))
    )
    (net (code "18") (name "ENC3A") (class "Default")
      (node (ref "CN3") (pin "2") (pinfunction "2_2") (pintype "passive"))
      (node (ref "IC1") (pin "6") (pinfunction "A5_6") (pintype "input"))
      (node (ref "R10") (pin "1") (pinfunction "1_1") (pintype "passive"))
      (node (ref "SV3") (pin "6") (pinfunction "6_6") (pintype "passive"))
    )
    (net (code "19") (name "ENC3B") (class "Default")
      (node (ref "CN3") (pin "3") (pinfunction "3_3") (pintype "passive"))
      (node (ref "IC1") (pin "7") (pinfunction "A6_7") (pintype "input"))
      (node (ref "R23") (pin "1") (pinfunction "1_1") (pintype "passive"))
      (node (ref "SV3") (pin "8") (pinfunction "8_8") (pintype "passive"))
    )
    (net (code "20") (name "ENC4A") (class "Default")
      (node (ref "CN4") (pin "2") (pinfunction "2_2") (pintype "passive"))
      (node (ref "IC1") (pin "8") (pinfunction "A7_8") (pintype "input"))
      (node (ref "R30") (pin "1") (pinfunction "1_1") (pintype "passive"))
      (node (ref "SV4") (pin "6") (pinfunction "6_6") (pintype "passive"))
    )
    (net (code "21") (name "ENC4B") (class "Default")
      (node (ref "CN4") (pin "3") (pinfunction "3_3") (pintype "passive"))
      (node (ref "IC1") (pin "9") (pinfunction "A8_9") (pintype "input"))
      (node (ref "R31") (pin "1") (pinfunction "1_1") (pintype "passive"))
      (node (ref "SV4") (pin "8") (pinfunction "8_8") (pintype "passive"))
    )
    (net (code "22") (name "GND") (class "Default")
      (node (ref "AQM0802A-RN-GBW") (pin "P$6") (pinfunction "VSS_P$6") (pintype "bidirectional"))
      (node (ref "C1") (pin "-") (pinfunction "-_-") (pintype "passive"))
      (node (ref "C10") (pin "2") (pinfunction "2_2") (pintype "passive"))
      (node (ref "C11") (pin "2") (pinfunction "2_2") (pintype "passive"))
      (node (ref "C12") (pin "1") (pinfunction "1_1") (pintype "passive"))
      (node (ref "C13") (pin "-") (pinfunction "-_-") (pintype "passive"))
      (node (ref "C14") (pin "2") (pinfunction "2_2") (pintype "passive"))
      (node (ref "C15") (pin "2") (pinfunction "2_2") (pintype "passive"))
      (node (ref "C16") (pin "2") (pinfunction "2_2") (pintype "passive"))
      (node (ref "C17") (pin "2") (pinfunction "2_2") (pintype "passive"))
      (node (ref "C18") (pin "2") (pinfunction "2_2") (pintype "passive"))
      (node (ref "C19") (pin "2") (pinfunction "2_2") (pintype "passive"))
      (node (ref "C20") (pin "2") (pinfunction "2_2") (pintype "passive"))
      (node (ref "C21") (pin "2") (pinfunction "2_2") (pintype "passive"))
      (node (ref "C22") (pin "2") (pinfunction "2_2") (pintype "passive"))
      (node (ref "C23") (pin "2") (pinfunction "2_2") (pintype "passive"))
      (node (ref "C24") (pin "2") (pinfunction "2_2") (pintype "passive"))
      (node (ref "C25") (pin "2") (pinfunction "2_2") (pintype "passive"))
      (node (ref "C26") (pin "2") (pinfunction "2_2") (pintype "passive"))
      (node (ref "C27") (pin "2") (pinfunction "2_2") (pintype "passive"))
      (node (ref "C28") (pin "2") (pinfunction "2_2") (pintype "passive"))
      (node (ref "C29") (pin "2") (pinfunction "2_2") (pintype "passive"))
      (node (ref "C3") (pin "2") (pinfunction "2_2") (pintype "passive"))
      (node (ref "C30") (pin "2") (pinfunction "2_2") (pintype "passive"))
      (node (ref "C31") (pin "2") (pinfunction "2_2") (pintype "passive"))
      (node (ref "C32") (pin "2") (pinfunction "2_2") (pintype "passive"))
      (node (ref "C33") (pin "-") (pinfunction "-_-") (pintype "passive"))
      (node (ref "C5") (pin "-") (pinfunction "-_-") (pintype "passive"))
      (node (ref "C6") (pin "2") (pinfunction "2_2") (pintype "passive"))
      (node (ref "C7") (pin "2") (pinfunction "2_2") (pintype "passive"))
      (node (ref "C8") (pin "2") (pinfunction "2_2") (pintype "passive"))
      (node (ref "C9") (pin "2") (pinfunction "2_2") (pintype "passive"))
      (node (ref "CN1") (pin "4") (pinfunction "4_4") (pintype "passive"))
      (node (ref "CN2") (pin "4") (pinfunction "4_4") (pintype "passive"))
      (node (ref "CN3") (pin "4") (pinfunction "4_4") (pintype "passive"))
      (node (ref "CN4") (pin "4") (pinfunction "4_4") (pintype "passive"))
      (node (ref "CN5") (pin "4") (pinfunction "4_4") (pintype "passive"))
      (node (ref "CN6") (pin "4") (pinfunction "4_4") (pintype "passive"))
      (node (ref "D1") (pin "1") (pinfunction "C0_1") (pintype "passive"))
      (node (ref "D1") (pin "2") (pinfunction "C1_2") (pintype "passive"))
      (node (ref "IC1") (pin "1") (pinfunction "G1_1") (pintype "input"))
      (node (ref "IC1") (pin "10") (pinfunction "GND_10") (pintype "power_in"))
      (node (ref "IC1") (pin "19") (pinfunction "G2_19") (pintype "input"))
      (node (ref "IC2") (pin "1") (pinfunction "GND_1") (pintype "input"))
      (node (ref "IC3") (pin "18") (pinfunction "GND_18") (pintype "power_in"))
      (node (ref "IC3") (pin "21") (pinfunction "GND_21") (pintype "power_in"))
      (node (ref "IC3") (pin "25") (pinfunction "AGND_25") (pintype "power_in"))
      (node (ref "IC3") (pin "26") (pinfunction "TEST_26") (pintype "bidirectional"))
      (node (ref "IC3") (pin "7") (pinfunction "GND_7") (pintype "power_in"))
      (node (ref "JP2") (pin "5") (pinfunction "5_5") (pintype "passive"))
      (node (ref "JP2") (pin "6") (pinfunction "6_6") (pintype "passive"))
      (node (ref "JP3") (pin "5") (pinfunction "5_5") (pintype "passive"))
      (node (ref "JP3") (pin "6") (pinfunction "6_6") (pintype "passive"))
      (node (ref "JP4") (pin "5") (pinfunction "5_5") (pintype "passive"))
      (node (ref "JP4") (pin "6") (pinfunction "6_6") (pintype "passive"))
      (node (ref "JP5") (pin "5") (pinfunction "5_5") (pintype "passive"))
      (node (ref "JP5") (pin "6") (pinfunction "6_6") (pintype "passive"))
      (node (ref "JP6") (pin "10") (pinfunction "10_10") (pintype "passive"))
      (node (ref "JP6") (pin "2") (pinfunction "2_2") (pintype "passive"))
      (node (ref "JP6") (pin "4") (pinfunction "4_4") (pintype "passive"))
      (node (ref "JP6") (pin "6") (pinfunction "6_6") (pintype "passive"))
      (node (ref "JP6") (pin "8") (pinfunction "8_8") (pintype "passive"))
      (node (ref "JP7") (pin "2") (pinfunction "2_2") (pintype "passive"))
      (node (ref "Q2") (pin "E") (pinfunction "E_E") (pintype "passive"))
      (node (ref "Q3") (pin "E") (pinfunction "E_E") (pintype "passive"))
      (node (ref "Q4") (pin "E") (pinfunction "E_E") (pintype "passive"))
      (node (ref "Q5") (pin "E") (pinfunction "E_E") (pintype "passive"))
      (node (ref "R1") (pin "2") (pinfunction "2_2") (pintype "passive"))
      (node (ref "R12") (pin "1") (pinfunction "1_1") (pintype "passive"))
      (node (ref "R15") (pin "1") (pinfunction "1_1") (pintype "passive"))
      (node (ref "R18") (pin "1") (pinfunction "1_1") (pintype "passive"))
      (node (ref "R24") (pin "1") (pinfunction "1_1") (pintype "passive"))
      (node (ref "R27") (pin "2") (pinfunction "2_2") (pintype "passive"))
      (node (ref "R51") (pin "1") (pinfunction "1_1") (pintype "passive"))
      (node (ref "S1") (pin "2") (pinfunction "P_2") (pintype "passive"))
      (node (ref "S2") (pin "2") (pinfunction "P_2") (pintype "passive"))
      (node (ref "S3") (pin "2") (pinfunction "P_2") (pintype "passive"))
      (node (ref "S4") (pin "2") (pinfunction "P_2") (pintype "passive"))
      (node (ref "S5") (pin "1") (pinfunction "S_1") (pintype "passive"))
      (node (ref "S5") (pin "2") (pinfunction "S1_2") (pintype "passive"))
      (node (ref "S6") (pin "1") (pinfunction "S_1") (pintype "passive"))
      (node (ref "S6") (pin "2") (pinfunction "S1_2") (pintype "passive"))
      (node (ref "S7") (pin "1") (pinfunction "S_1") (pintype "passive"))
      (node (ref "S7") (pin "2") (pinfunction "S1_2") (pintype "passive"))
      (node (ref "S8") (pin "1") (pinfunction "S_1") (pintype "passive"))
      (node (ref "S8") (pin "2") (pinfunction "S1_2") (pintype "passive"))
      (node (ref "S9") (pin "1") (pinfunction "S_1") (pintype "passive"))
      (node (ref "S9") (pin "2") (pinfunction "S1_2") (pintype "passive"))
      (node (ref "SV1") (pin "3") (pinfunction "3_3") (pintype "passive"))
      (node (ref "SV2") (pin "3") (pinfunction "3_3") (pintype "passive"))
      (node (ref "SV3") (pin "3") (pinfunction "3_3") (pintype "passive"))
      (node (ref "SV4") (pin "3") (pinfunction "3_3") (pintype "passive"))
      (node (ref "U$1") (pin "6") (pinfunction "GND_6") (pintype "bidirectional"))
      (node (ref "U$1") (pin "GND1") (pinfunction "SHIELD_GND1") (pintype "bidirectional"))
      (node (ref "U$1") (pin "GND2") (pinfunction "SHIELD_GND2") (pintype "bidirectional"))
      (node (ref "U$1") (pin "GND3") (pinfunction "SHIELD_GND3") (pintype "bidirectional"))
      (node (ref "U$1") (pin "GND4") (pinfunction "SHIELD_GND4") (pintype "bidirectional"))
      (node (ref "U$10") (pin "10") (pinfunction "GND_10") (pintype "bidirectional"))
      (node (ref "U$10") (pin "9") (pinfunction "AD0_9") (pintype "bidirectional"))
      (node (ref "U$11") (pin "14") (pinfunction "AGND_14") (pintype "bidirectional"))
      (node (ref "U$11") (pin "9") (pinfunction "DGND_9") (pintype "bidirectional"))
      (node (ref "U$12") (pin "4") (pinfunction "GND_4") (pintype "power_in"))
      (node (ref "U$12") (pin "6") (pinfunction "I_6") (pintype "input"))
      (node (ref "U$13") (pin "1") (pinfunction "ON/OFF_1") (pintype "bidirectional"))
      (node (ref "U$13") (pin "3") (pinfunction "GND_3") (pintype "bidirectional"))
      (node (ref "U$13") (pin "7") (pinfunction "GND/2_7") (pintype "bidirectional"))
      (node (ref "U$14") (pin "2") (pinfunction "2_2") (pintype "passive"))
      (node (ref "U$14") (pin "4") (pinfunction "4_4") (pintype "passive"))
      (node (ref "U$2") (pin "6") (pinfunction "6_6") (pintype "passive"))
      (node (ref "U$3") (pin "6") (pinfunction "6_6") (pintype "passive"))
      (node (ref "U$4") (pin "1") (pinfunction "1_1") (pintype "passive"))
      (node (ref "U$5") (pin "6") (pinfunction "6_6") (pintype "passive"))
      (node (ref "U$6") (pin "6") (pinfunction "6_6") (pintype "passive"))
      (node (ref "U$7") (pin "6") (pinfunction "6_6") (pintype "passive"))
      (node (ref "U$8") (pin "2") (pinfunction "GND_2") (pintype "power_in"))
      (node (ref "U$9") (pin "10") (pinfunction "VSS_1_10") (pintype "bidirectional"))
      (node (ref "U$9") (pin "20") (pinfunction "VSSA_20") (pintype "bidirectional"))
      (node (ref "U$9") (pin "27") (pinfunction "VSS_2_27") (pintype "bidirectional"))
      (node (ref "U$9") (pin "74") (pinfunction "VSS_3_74") (pintype "bidirectional"))
      (node (ref "U$9") (pin "99") (pinfunction "VSS_4_99") (pintype "bidirectional"))
      (node (ref "X1") (pin "5") (pinfunction "5_5") (pintype "input"))
      (node (ref "X2") (pin "2") (pinfunction "2_2") (pintype "passive"))
      (node (ref "X3") (pin "2") (pinfunction "2_2") (pintype "passive"))
      (node (ref "X4") (pin "5") (pinfunction "5_5") (pintype "input"))
      (node (ref "XB1") (pin "10") (pinfunction "GND_10") (pintype "power_in"))
    )
    (net (code "23") (name "Net-(AQM0802A-RN-GBW-CAP1N)") (class "Default")
      (node (ref "AQM0802A-RN-GBW") (pin "P$3") (pinfunction "CAP1N_P$3") (pintype "bidirectional"))
      (node (ref "C2") (pin "1") (pinfunction "1_1") (pintype "passive"))
    )
    (net (code "24") (name "Net-(AQM0802A-RN-GBW-CAP1P)") (class "Default")
      (node (ref "AQM0802A-RN-GBW") (pin "P$4") (pinfunction "CAP1P_P$4") (pintype "bidirectional"))
      (node (ref "C2") (pin "2") (pinfunction "2_2") (pintype "passive"))
    )
    (net (code "25") (name "Net-(AQM0802A-RN-GBW-VOUT)") (class "Default")
      (node (ref "AQM0802A-RN-GBW") (pin "P$2") (pinfunction "VOUT_P$2") (pintype "bidirectional"))
      (node (ref "C4") (pin "2") (pinfunction "2_2") (pintype "passive"))
    )
    (net (code "26") (name "Net-(D1-A0)") (class "Default")
      (node (ref "D1") (pin "4") (pinfunction "A0_4") (pintype "passive"))
      (node (ref "R54") (pin "1") (pinfunction "1_1") (pintype "passive"))
    )
    (net (code "27") (name "Net-(D1-A1)") (class "Default")
      (node (ref "D1") (pin "3") (pinfunction "A1_3") (pintype "passive"))
      (node (ref "R53") (pin "1") (pinfunction "1_1") (pintype "passive"))
    )
    (net (code "28") (name "Net-(IC3-3V3OUT)") (class "Default")
      (node (ref "C21") (pin "1") (pinfunction "1_1") (pintype "passive"))
      (node (ref "IC3") (pin "17") (pinfunction "3V3OUT_17") (pintype "output"))
      (node (ref "IC3") (pin "4") (pinfunction "VCCIO_4") (pintype "power_in"))
    )
    (net (code "29") (name "Net-(IC3-USBDM)") (class "Default")
      (node (ref "IC3") (pin "16") (pinfunction "USBDM_16") (pintype "bidirectional"))
      (node (ref "X1") (pin "2") (pinfunction "2_2") (pintype "input"))
    )
    (net (code "30") (name "Net-(IC3-USBDP)") (class "Default")
      (node (ref "IC3") (pin "15") (pinfunction "USBDP_15") (pintype "bidirectional"))
      (node (ref "X1") (pin "3") (pinfunction "3_3") (pintype "input"))
    )
    (net (code "31") (name "Net-(IC3-VCC)") (class "Default")
      (node (ref "C11") (pin "1") (pinfunction "1_1") (pintype "passive"))
      (node (ref "IC3") (pin "20") (pinfunction "VCC_20") (pintype "power_in"))
      (node (ref "X1") (pin "1") (pinfunction "1_1") (pintype "input"))
    )
    (net (code "32") (name "Net-(JP1-Pad2)") (class "Default")
      (node (ref "JP1") (pin "2") (pinfunction "2_2") (pintype "passive"))
      (node (ref "R4") (pin "2") (pinfunction "2_2") (pintype "passive"))
    )
    (net (code "33") (name "Net-(LED1-PadC)") (class "Default")
      (node (ref "LED1") (pin "C") (pinfunction "C_C") (pintype "passive"))
      (node (ref "R11") (pin "2") (pinfunction "2_2") (pintype "passive"))
    )
    (net (code "34") (name "Net-(LED2-PadC)") (class "Default")
      (node (ref "LED2") (pin "C") (pinfunction "C_C") (pintype "passive"))
      (node (ref "R14") (pin "2") (pinfunction "2_2") (pintype "passive"))
    )
    (net (code "35") (name "Net-(LED3-PadC)") (class "Default")
      (node (ref "LED3") (pin "C") (pinfunction "C_C") (pintype "passive"))
      (node (ref "R17") (pin "2") (pinfunction "2_2") (pintype "passive"))
    )
    (net (code "36") (name "Net-(LED4-PadC)") (class "Default")
      (node (ref "LED4") (pin "C") (pinfunction "C_C") (pintype "passive"))
      (node (ref "R22") (pin "2") (pinfunction "2_2") (pintype "passive"))
    )
    (net (code "37") (name "Net-(Q2-PadB)") (class "Default")
      (node (ref "Q2") (pin "B") (pinfunction "B_B") (pintype "passive"))
      (node (ref "R12") (pin "2") (pinfunction "2_2") (pintype "passive"))
      (node (ref "R13") (pin "2") (pinfunction "2_2") (pintype "passive"))
    )
    (net (code "38") (name "Net-(Q2-PadC)") (class "Default")
      (node (ref "Q2") (pin "C") (pinfunction "C_C") (pintype "passive"))
      (node (ref "R11") (pin "1") (pinfunction "1_1") (pintype "passive"))
    )
    (net (code "39") (name "Net-(Q3-PadB)") (class "Default")
      (node (ref "Q3") (pin "B") (pinfunction "B_B") (pintype "passive"))
      (node (ref "R15") (pin "2") (pinfunction "2_2") (pintype "passive"))
      (node (ref "R16") (pin "2") (pinfunction "2_2") (pintype "passive"))
    )
    (net (code "40") (name "Net-(Q3-PadC)") (class "Default")
      (node (ref "Q3") (pin "C") (pinfunction "C_C") (pintype "passive"))
      (node (ref "R14") (pin "1") (pinfunction "1_1") (pintype "passive"))
    )
    (net (code "41") (name "Net-(Q4-PadB)") (class "Default")
      (node (ref "Q4") (pin "B") (pinfunction "B_B") (pintype "passive"))
      (node (ref "R18") (pin "2") (pinfunction "2_2") (pintype "passive"))
      (node (ref "R19") (pin "2") (pinfunction "2_2") (pintype "passive"))
    )
    (net (code "42") (name "Net-(Q4-PadC)") (class "Default")
      (node (ref "Q4") (pin "C") (pinfunction "C_C") (pintype "passive"))
      (node (ref "R17") (pin "1") (pinfunction "1_1") (pintype "passive"))
    )
    (net (code "43") (name "Net-(Q5-PadB)") (class "Default")
      (node (ref "Q5") (pin "B") (pinfunction "B_B") (pintype "passive"))
      (node (ref "R24") (pin "2") (pinfunction "2_2") (pintype "passive"))
      (node (ref "R25") (pin "2") (pinfunction "2_2") (pintype "passive"))
    )
    (net (code "44") (name "Net-(Q5-PadC)") (class "Default")
      (node (ref "Q5") (pin "C") (pinfunction "C_C") (pintype "passive"))
      (node (ref "R22") (pin "1") (pinfunction "1_1") (pintype "passive"))
    )
    (net (code "45") (name "Net-(R6-Pad2)") (class "Default")
      (node (ref "R6") (pin "2") (pinfunction "2_2") (pintype "passive"))
      (node (ref "X4") (pin "2") (pinfunction "2_2") (pintype "input"))
    )
    (net (code "46") (name "Net-(R9-Pad2)") (class "Default")
      (node (ref "R9") (pin "2") (pinfunction "2_2") (pintype "passive"))
      (node (ref "X4") (pin "3") (pinfunction "3_3") (pintype "input"))
    )
    (net (code "47") (name "Net-(R26-Pad2)") (class "Default")
      (node (ref "R26") (pin "2") (pinfunction "2_2") (pintype "passive"))
      (node (ref "R27") (pin "1") (pinfunction "1_1") (pintype "passive"))
    )
    (net (code "48") (name "Net-(SJ5-Pad1)") (class "Default")
      (node (ref "SJ5") (pin "1") (pinfunction "1_1") (pintype "passive"))
      (node (ref "X3") (pin "4") (pinfunction "4_4") (pintype "passive"))
    )
    (net (code "49") (name "Net-(SP1-1)") (class "Default")
      (node (ref "SP1") (pin "-") (pinfunction "1_-") (pintype "passive"))
      (node (ref "U$12") (pin "3") (pinfunction "I_3") (pintype "input"))
      (node (ref "U$12") (pin "7") (pinfunction "O_7") (pintype "output"))
    )
    (net (code "50") (name "Net-(SP1-2)") (class "Default")
      (node (ref "SP1") (pin "+") (pinfunction "2_+") (pintype "passive"))
      (node (ref "U$12") (pin "5") (pinfunction "O_5") (pintype "output"))
    )
    (net (code "51") (name "Net-(U$8A-RS)") (class "Default")
      (node (ref "R51") (pin "2") (pinfunction "2_2") (pintype "passive"))
      (node (ref "U$8") (pin "8") (pinfunction "RS_8") (pintype "bidirectional"))
    )
    (net (code "52") (name "Net-(U$9-BOOT0)") (class "Default")
      (node (ref "R1") (pin "1") (pinfunction "1_1") (pintype "passive"))
      (node (ref "U$9") (pin "94") (pinfunction "BOOT0_94") (pintype "bidirectional"))
    )
    (net (code "53") (name "Net-(U$9-PA13{slash}JTMS-SWDAT(5T))") (class "Default")
      (node (ref "U$4") (pin "2") (pinfunction "2_2") (pintype "passive"))
      (node (ref "U$9") (pin "72") (pinfunction "PA13/JTMS-SWDAT(5T)_72") (pintype "bidirectional"))
    )
    (net (code "54") (name "Net-(U$9-PA14{slash}JTCK-SWCLK(5T))") (class "Default")
      (node (ref "U$4") (pin "3") (pinfunction "3_3") (pintype "passive"))
      (node (ref "U$9") (pin "76") (pinfunction "PA14/JTCK-SWCLK(5T)_76") (pintype "bidirectional"))
    )
    (net (code "55") (name "Net-(U$9-PH0-OSC_IN(5T))") (class "Default")
      (node (ref "C15") (pin "1") (pinfunction "1_1") (pintype "passive"))
      (node (ref "U$14") (pin "3") (pinfunction "3_3") (pintype "passive"))
      (node (ref "U$9") (pin "12") (pinfunction "PH0-OSC_IN(5T)_12") (pintype "bidirectional"))
    )
    (net (code "56") (name "Net-(U$9-PH1-OSC_OUT(5T))") (class "Default")
      (node (ref "C20") (pin "1") (pinfunction "1_1") (pintype "passive"))
      (node (ref "U$14") (pin "1") (pinfunction "1_1") (pintype "passive"))
      (node (ref "U$9") (pin "13") (pinfunction "PH1-OSC_OUT(5T)_13") (pintype "bidirectional"))
    )
    (net (code "57") (name "Net-(U$9-VCAP1)") (class "Default")
      (node (ref "C23") (pin "1") (pinfunction "1_1") (pintype "passive"))
      (node (ref "U$9") (pin "49") (pinfunction "VCAP1_49") (pintype "bidirectional"))
    )
    (net (code "58") (name "Net-(U$9-VCAP2)") (class "Default")
      (node (ref "C24") (pin "1") (pinfunction "1_1") (pintype "passive"))
      (node (ref "U$9") (pin "73") (pinfunction "VCAP2_73") (pintype "bidirectional"))
    )
    (net (code "59") (name "Net-(U$11-VDD)") (class "Default")
      (node (ref "BK2125HM121-T") (pin "2") (pinfunction "2_2") (pintype "passive"))
      (node (ref "C32") (pin "1") (pinfunction "1_1") (pintype "passive"))
      (node (ref "U$11") (pin "15") (pinfunction "VREF_15") (pintype "bidirectional"))
      (node (ref "U$11") (pin "16") (pinfunction "VDD_16") (pintype "bidirectional"))
    )
    (net (code "60") (name "Net-(U$13-TRIM)") (class "Default")
      (node (ref "R26") (pin "1") (pinfunction "1_1") (pintype "passive"))
      (node (ref "U$13") (pin "6") (pinfunction "TRIM_6") (pintype "bidirectional"))
    )
    (net (code "61") (name "PA0_TIM5_CH1") (class "Default")
      (node (ref "IC1") (pin "18") (pinfunction "Y1_18") (pintype "tri_state"))
      (node (ref "U$9") (pin "23") (pinfunction "PA0/ETH_MII_CRS/ADC123_IN0(5T)_23") (pintype "bidirectional"))
    )
    (net (code "62") (name "PA1_TIM5_CH2") (class "Default")
      (node (ref "IC1") (pin "17") (pinfunction "Y2_17") (pintype "tri_state"))
      (node (ref "U$9") (pin "24") (pinfunction "PA1/ETH_RMII_RX_CLK/ADC123_IN1(5T)_24") (pintype "bidirectional"))
    )
    (net (code "63") (name "PA2_TIM2_CH3") (class "Default")
      (node (ref "JP7") (pin "5") (pinfunction "5_5") (pintype "passive"))
      (node (ref "U$9") (pin "25") (pinfunction "PA2/ETH_MDIO/ADC123_IN2(5T)_25") (pintype "bidirectional"))
    )
    (net (code "64") (name "PA3_TIM2_CH4") (class "Default")
      (node (ref "JP7") (pin "6") (pinfunction "6_6") (pintype "passive"))
      (node (ref "U$9") (pin "26") (pinfunction "PA3/ETH_MII_COL/ADC123_IN2(5T)_26") (pintype "bidirectional"))
    )
    (net (code "65") (name "PA4_SPI1_SS0") (class "Default")
      (node (ref "U$5") (pin "5") (pinfunction "5_5") (pintype "passive"))
      (node (ref "U$9") (pin "29") (pinfunction "PA4/ADC12_IN4_29") (pintype "bidirectional"))
    )
    (net (code "66") (name "PA5_SPI1_SCK") (class "Default")
      (node (ref "U$5") (pin "4") (pinfunction "4_4") (pintype "passive"))
      (node (ref "U$6") (pin "4") (pinfunction "4_4") (pintype "passive"))
      (node (ref "U$7") (pin "4") (pinfunction "4_4") (pintype "passive"))
      (node (ref "U$9") (pin "30") (pinfunction "PA5/SPI1_SCK/ADC12_IN5_30") (pintype "bidirectional"))
    )
    (net (code "67") (name "PA6_TIM3_CH1") (class "Default")
      (node (ref "IC1") (pin "16") (pinfunction "Y3_16") (pintype "tri_state"))
      (node (ref "U$9") (pin "31") (pinfunction "PA6/SPI1_MISO/ADC12_IN6(5T)_31") (pintype "bidirectional"))
    )
    (net (code "68") (name "PA7_TIM3_CH2") (class "Default")
      (node (ref "IC1") (pin "15") (pinfunction "Y4_15") (pintype "tri_state"))
      (node (ref "U$9") (pin "32") (pinfunction "PA7/ETH_MII_RX_DV/ADC12_IN7(5T)_32") (pintype "bidirectional"))
    )
    (net (code "69") (name "PA9_USB_VBUS") (class "Default")
      (node (ref "U$9") (pin "68") (pinfunction "PA9/USART1_TX(5T)_68") (pintype "bidirectional"))
      (node (ref "X4") (pin "1") (pinfunction "1_1") (pintype "input"))
    )
    (net (code "70") (name "PA10_USB_ID") (class "Default")
      (node (ref "U$9") (pin "69") (pinfunction "PA10/USART1_RX(5T)_69") (pintype "bidirectional"))
      (node (ref "X4") (pin "4") (pinfunction "4_4") (pintype "input"))
    )
    (net (code "71") (name "PA11_USB_DM") (class "Default")
      (node (ref "R6") (pin "1") (pinfunction "1_1") (pintype "passive"))
      (node (ref "U$9") (pin "70") (pinfunction "PA11/USART1_CTS(5T)_70") (pintype "bidirectional"))
    )
    (net (code "72") (name "PA12_USB_DP") (class "Default")
      (node (ref "R9") (pin "1") (pinfunction "1_1") (pintype "passive"))
      (node (ref "U$9") (pin "71") (pinfunction "PA12/USART1_RTS(5T)_71") (pintype "bidirectional"))
    )
    (net (code "73") (name "PA15_TIM2_CH1") (class "Default")
      (node (ref "JP7") (pin "3") (pinfunction "3_3") (pintype "passive"))
      (node (ref "U$9") (pin "77") (pinfunction "PA15/JTDI(5T)_77") (pintype "bidirectional"))
    )
    (net (code "74") (name "PB0") (class "Default")
      (node (ref "JP6") (pin "9") (pinfunction "9_9") (pintype "passive"))
      (node (ref "U$9") (pin "35") (pinfunction "PB0/ETH_MII_RXD2/ADC12_IN8(5T)_35") (pintype "bidirectional"))
    )
    (net (code "75") (name "PB1") (class "Default")
      (node (ref "JP6") (pin "7") (pinfunction "7_7") (pintype "passive"))
      (node (ref "U$9") (pin "36") (pinfunction "PB1/ETH_MII_RXD3/ADC12_IN9(5T)_36") (pintype "bidirectional"))
    )
    (net (code "76") (name "PB2") (class "Default")
      (node (ref "JP6") (pin "5") (pinfunction "5_5") (pintype "passive"))
      (node (ref "U$9") (pin "37") (pinfunction "PB2/BOOT1(5T)_37") (pintype "bidirectional"))
    )
    (net (code "77") (name "PB3_TIM2_CH2") (class "Default")
      (node (ref "JP7") (pin "4") (pinfunction "4_4") (pintype "passive"))
      (node (ref "U$9") (pin "89") (pinfunction "PB3/JTDO(5T)_89") (pintype "bidirectional"))
    )
    (net (code "78") (name "PB4_SPI1_MISO") (class "Default")
      (node (ref "U$5") (pin "2") (pinfunction "2_2") (pintype "passive"))
      (node (ref "U$6") (pin "2") (pinfunction "2_2") (pintype "passive"))
      (node (ref "U$7") (pin "2") (pinfunction "2_2") (pintype "passive"))
      (node (ref "U$9") (pin "90") (pinfunction "PB4/JNTRST(5T)_90") (pintype "bidirectional"))
    )
    (net (code "79") (name "PB5_SPI1_MOSI") (class "Default")
      (node (ref "U$5") (pin "3") (pinfunction "3_3") (pintype "passive"))
      (node (ref "U$6") (pin "3") (pinfunction "3_3") (pintype "passive"))
      (node (ref "U$7") (pin "3") (pinfunction "3_3") (pintype "passive"))
      (node (ref "U$9") (pin "91") (pinfunction "PB5/TIM3_CH2(5T)_91") (pintype "bidirectional"))
    )
    (net (code "80") (name "PB6_USART1_TX") (class "Default")
      (node (ref "U$9") (pin "92") (pinfunction "PB6/I2C1_SCL(5T)_92") (pintype "bidirectional"))
      (node (ref "XB1") (pin "3") (pinfunction "DIN/~{CONFIG}_3") (pintype "input"))
    )
    (net (code "81") (name "PB7_USART1_RX") (class "Default")
      (node (ref "U$9") (pin "93") (pinfunction "PB7/I2C1_SDA(5T)_93") (pintype "bidirectional"))
      (node (ref "XB1") (pin "2") (pinfunction "DOUT_2") (pintype "output"))
    )
    (net (code "82") (name "PB8_I2C1_SCL") (class "Default")
      (node (ref "AQM0802A-RN-GBW") (pin "P$8") (pinfunction "SCL_P$8") (pintype "bidirectional"))
      (node (ref "R20") (pin "1") (pinfunction "1_1") (pintype "passive"))
      (node (ref "U$10") (pin "3") (pinfunction "SCL_3") (pintype "bidirectional"))
      (node (ref "U$9") (pin "95") (pinfunction "PB8/TIM10_CH1(5T)_95") (pintype "bidirectional"))
    )
    (net (code "83") (name "PB9_I2C1_SDA") (class "Default")
      (node (ref "AQM0802A-RN-GBW") (pin "P$7") (pinfunction "SDA_P$7") (pintype "bidirectional"))
      (node (ref "R21") (pin "1") (pinfunction "1_1") (pintype "passive"))
      (node (ref "U$10") (pin "4") (pinfunction "SDA_4") (pintype "bidirectional"))
      (node (ref "U$9") (pin "96") (pinfunction "PB9/TIM11_CH1(5T)_96") (pintype "bidirectional"))
    )
    (net (code "84") (name "PB10_SPI2_SS0") (class "Default")
      (node (ref "U$2") (pin "5") (pinfunction "5_5") (pintype "passive"))
      (node (ref "U$9") (pin "47") (pinfunction "PB10/ETH_MII_RX_ER(5T)_47") (pintype "bidirectional"))
    )
    (net (code "85") (name "PB11_SPI2_SS1") (class "Default")
      (node (ref "U$3") (pin "5") (pinfunction "5_5") (pintype "passive"))
      (node (ref "U$9") (pin "48") (pinfunction "PB11/ETH_MII_TX_EN(5T)_48") (pintype "bidirectional"))
    )
    (net (code "86") (name "PB12_SPI2_SS2") (class "Default")
      (node (ref "U$11") (pin "10") (pinfunction "~{CS}_10") (pintype "bidirectional"))
      (node (ref "U$9") (pin "51") (pinfunction "PB12/ETH_MII_TXD0(5T)_51") (pintype "bidirectional"))
    )
    (net (code "87") (name "PB13_SPI2_SCK") (class "Default")
      (node (ref "U$11") (pin "13") (pinfunction "CLK_13") (pintype "bidirectional"))
      (node (ref "U$2") (pin "4") (pinfunction "4_4") (pintype "passive"))
      (node (ref "U$3") (pin "4") (pinfunction "4_4") (pintype "passive"))
      (node (ref "U$9") (pin "52") (pinfunction "PB13/ETH_MII_TXD1(5T)_52") (pintype "bidirectional"))
    )
    (net (code "88") (name "PB14_SPI2_MISO") (class "Default")
      (node (ref "U$11") (pin "12") (pinfunction "DOUT_12") (pintype "bidirectional"))
      (node (ref "U$2") (pin "2") (pinfunction "2_2") (pintype "passive"))
      (node (ref "U$3") (pin "2") (pinfunction "2_2") (pintype "passive"))
      (node (ref "U$9") (pin "53") (pinfunction "PB14/TIM8_CH2N(5T)_53") (pintype "bidirectional"))
    )
    (net (code "89") (name "PB15_SPI2_MOSI") (class "Default")
      (node (ref "U$11") (pin "11") (pinfunction "DIN_11") (pintype "bidirectional"))
      (node (ref "U$2") (pin "3") (pinfunction "3_3") (pintype "passive"))
      (node (ref "U$3") (pin "3") (pinfunction "3_3") (pintype "passive"))
      (node (ref "U$9") (pin "54") (pinfunction "PB15/TIM8_CH3N(5T)_54") (pintype "bidirectional"))
    )
    (net (code "90") (name "PC6_TIM8_CH1") (class "Default")
      (node (ref "IC1") (pin "12") (pinfunction "Y7_12") (pintype "tri_state"))
      (node (ref "U$9") (pin "63") (pinfunction "PC6/TIM3_CH1(5T)_63") (pintype "bidirectional"))
    )
    (net (code "91") (name "PC7_TIM8_CH2") (class "Default")
      (node (ref "IC1") (pin "11") (pinfunction "Y8_11") (pintype "tri_state"))
      (node (ref "U$9") (pin "64") (pinfunction "PC7/TIM8_CH2(5T)_64") (pintype "bidirectional"))
    )
    (net (code "92") (name "PC8_SDIO_D0") (class "Default")
      (node (ref "U$1") (pin "7") (pinfunction "DO_7") (pintype "bidirectional"))
      (node (ref "U$9") (pin "65") (pinfunction "PC8/TIM8_CH3(5T)_65") (pintype "bidirectional"))
    )
    (net (code "93") (name "PC9_SDIO_D1") (class "Default")
      (node (ref "U$1") (pin "8") (pinfunction "RSV_8") (pintype "bidirectional"))
      (node (ref "U$9") (pin "66") (pinfunction "PC9/TIM3_CH4(5T)_66") (pintype "bidirectional"))
    )
    (net (code "94") (name "PC10_SDIO_D2") (class "Default")
      (node (ref "U$1") (pin "1") (pinfunction "NC_1") (pintype "bidirectional"))
      (node (ref "U$9") (pin "78") (pinfunction "PC10/UART4_TX(5T)_78") (pintype "bidirectional"))
    )
    (net (code "95") (name "PC11_SDIO_D3") (class "Default")
      (node (ref "U$1") (pin "2") (pinfunction "-CS_2") (pintype "bidirectional"))
      (node (ref "U$9") (pin "79") (pinfunction "PC11/UART4_RX(5T)_79") (pintype "bidirectional"))
    )
    (net (code "96") (name "PC12_SDIO_CK") (class "Default")
      (node (ref "U$1") (pin "5") (pinfunction "CLK_5") (pintype "bidirectional"))
      (node (ref "U$9") (pin "80") (pinfunction "PC12/UART5_TX(5T)_80") (pintype "bidirectional"))
    )
    (net (code "97") (name "PC13_LED0") (class "Default")
      (node (ref "R54") (pin "2") (pinfunction "2_2") (pintype "passive"))
      (node (ref "U$9") (pin "7") (pinfunction "PC13(5T)_7") (pintype "bidirectional"))
    )
    (net (code "98") (name "PD0_CAN1_RX") (class "Default")
      (node (ref "U$8") (pin "4") (pinfunction "RXD_4") (pintype "bidirectional"))
      (node (ref "U$9") (pin "81") (pinfunction "PD0/CAN1_RX(5T)_81") (pintype "bidirectional"))
    )
    (net (code "99") (name "PD1_CAN1_TX") (class "Default")
      (node (ref "U$8") (pin "1") (pinfunction "TXD_1") (pintype "bidirectional"))
      (node (ref "U$9") (pin "82") (pinfunction "PD1/CAN1_TX(5T)_82") (pintype "bidirectional"))
    )
    (net (code "100") (name "PD2_SDIO_CMD") (class "Default")
      (node (ref "U$1") (pin "3") (pinfunction "DI_3") (pintype "bidirectional"))
      (node (ref "U$9") (pin "83") (pinfunction "PD2/UART5_RX(5T)_83") (pintype "bidirectional"))
    )
    (net (code "101") (name "PD3_SPI1_SS1") (class "Default")
      (node (ref "U$6") (pin "5") (pinfunction "5_5") (pintype "passive"))
      (node (ref "U$9") (pin "84") (pinfunction "PD3(5T)_84") (pintype "bidirectional"))
    )
    (net (code "102") (name "PD4_SPI1_SS2") (class "Default")
      (node (ref "U$7") (pin "5") (pinfunction "5_5") (pintype "passive"))
      (node (ref "U$9") (pin "85") (pinfunction "PD4(5T)_85") (pintype "bidirectional"))
    )
    (net (code "103") (name "PD5_USART2_TX") (class "Default")
      (node (ref "IC3") (pin "5") (pinfunction "RXD_5") (pintype "input"))
      (node (ref "U$9") (pin "86") (pinfunction "PD5/USART2_TX(5T)_86") (pintype "bidirectional"))
    )
    (net (code "104") (name "PD6_USART2_RX") (class "Default")
      (node (ref "IC3") (pin "1") (pinfunction "TXD_1") (pintype "output"))
      (node (ref "U$9") (pin "87") (pinfunction "PD6/USART2_RX(5T)_87") (pintype "bidirectional"))
    )
    (net (code "105") (name "PD8_LED1") (class "Default")
      (node (ref "R13") (pin "1") (pinfunction "1_1") (pintype "passive"))
      (node (ref "U$9") (pin "55") (pinfunction "PD8/USART3_TX(5T)_55") (pintype "bidirectional"))
    )
    (net (code "106") (name "PD9_LED2") (class "Default")
      (node (ref "R16") (pin "1") (pinfunction "1_1") (pintype "passive"))
      (node (ref "U$9") (pin "56") (pinfunction "PD9/USART3_RX(5T)_56") (pintype "bidirectional"))
    )
    (net (code "107") (name "PD10_LED3") (class "Default")
      (node (ref "R19") (pin "1") (pinfunction "1_1") (pintype "passive"))
      (node (ref "U$9") (pin "57") (pinfunction "PD10(5T)_57") (pintype "bidirectional"))
    )
    (net (code "108") (name "PD11_LED4") (class "Default")
      (node (ref "R25") (pin "1") (pinfunction "1_1") (pintype "passive"))
      (node (ref "U$9") (pin "58") (pinfunction "PD11(5T)_58") (pintype "bidirectional"))
    )
    (net (code "109") (name "PD12_TIM4_CH1") (class "Default")
      (node (ref "JP7") (pin "9") (pinfunction "9_9") (pintype "passive"))
      (node (ref "U$9") (pin "59") (pinfunction "PD12/TIM4_CH1(5T)_59") (pintype "bidirectional"))
    )
    (net (code "110") (name "PD13_TIM4_CH2") (class "Default")
      (node (ref "JP7") (pin "10") (pinfunction "10_10") (pintype "passive"))
      (node (ref "U$9") (pin "60") (pinfunction "PD13/TIM4_CH2(5T)_60") (pintype "bidirectional"))
    )
    (net (code "111") (name "PD14_TIM4_CH3") (class "Default")
      (node (ref "JP7") (pin "7") (pinfunction "7_7") (pintype "passive"))
      (node (ref "U$9") (pin "61") (pinfunction "PD14/TIM4_CH3(5T)_61") (pintype "bidirectional"))
    )
    (net (code "112") (name "PD15_TIM4_CH4") (class "Default")
      (node (ref "JP7") (pin "8") (pinfunction "8_8") (pintype "passive"))
      (node (ref "U$9") (pin "62") (pinfunction "PD15/TIM4_CH4(5T)_62") (pintype "bidirectional"))
    )
    (net (code "113") (name "PE0_GYRO_INT") (class "Default")
      (node (ref "U$10") (pin "8") (pinfunction "INT_8") (pintype "bidirectional"))
      (node (ref "U$9") (pin "97") (pinfunction "PE0(5T)_97") (pintype "bidirectional"))
    )
    (net (code "114") (name "PE1_SW1") (class "Default")
      (node (ref "S5") (pin "3") (pinfunction "P_3") (pintype "passive"))
      (node (ref "S5") (pin "4") (pinfunction "P1_4") (pintype "passive"))
      (node (ref "U$9") (pin "98") (pinfunction "PE1(5T)_98") (pintype "bidirectional"))
    )
    (net (code "115") (name "PE2_SW2") (class "Default")
      (node (ref "S6") (pin "3") (pinfunction "P_3") (pintype "passive"))
      (node (ref "S6") (pin "4") (pinfunction "P1_4") (pintype "passive"))
      (node (ref "U$9") (pin "1") (pinfunction "PE2/ETH_MII_TXD3(5T)_1") (pintype "bidirectional"))
    )
    (net (code "116") (name "PE3_SW3") (class "Default")
      (node (ref "S7") (pin "3") (pinfunction "P_3") (pintype "passive"))
      (node (ref "S7") (pin "4") (pinfunction "P1_4") (pintype "passive"))
      (node (ref "U$9") (pin "2") (pinfunction "PE3(5T)_2") (pintype "bidirectional"))
    )
    (net (code "117") (name "PE4_SW4") (class "Default")
      (node (ref "S8") (pin "3") (pinfunction "P_3") (pintype "passive"))
      (node (ref "S8") (pin "4") (pinfunction "P1_4") (pintype "passive"))
      (node (ref "U$9") (pin "3") (pinfunction "PE4(5T)_3") (pintype "bidirectional"))
    )
    (net (code "118") (name "PE5_TIM9_CH1") (class "Default")
      (node (ref "U$12") (pin "1") (pinfunction "I_1") (pintype "input"))
      (node (ref "U$9") (pin "4") (pinfunction "PE5/TIM9_CH1(5T)_4") (pintype "bidirectional"))
    )
    (net (code "119") (name "PE7") (class "Default")
      (node (ref "JP6") (pin "3") (pinfunction "3_3") (pintype "passive"))
      (node (ref "U$9") (pin "38") (pinfunction "PE7/TIM1_ETR(5T)_38") (pintype "bidirectional"))
    )
    (net (code "120") (name "PE8") (class "Default")
      (node (ref "JP6") (pin "1") (pinfunction "1_1") (pintype "passive"))
      (node (ref "U$9") (pin "39") (pinfunction "PE8/TIM1_CH1N(5T)_39") (pintype "bidirectional"))
    )
    (net (code "121") (name "PE9_TIM1_CH1") (class "Default")
      (node (ref "IC1") (pin "14") (pinfunction "Y5_14") (pintype "tri_state"))
      (node (ref "U$9") (pin "40") (pinfunction "PE9/TIM1_CH1(5T)_40") (pintype "bidirectional"))
    )
    (net (code "122") (name "PE11_TIM1_CH2") (class "Default")
      (node (ref "IC1") (pin "13") (pinfunction "Y6_13") (pintype "tri_state"))
      (node (ref "U$9") (pin "42") (pinfunction "PE11/TIM1_CH2(5T)_42") (pintype "bidirectional"))
    )
    (net (code "123") (name "PE12_TOGGLE1") (class "Default")
      (node (ref "S1") (pin "1") (pinfunction "O_1") (pintype "passive"))
      (node (ref "U$9") (pin "43") (pinfunction "PE12/TIM1_CH3N(5T)_43") (pintype "bidirectional"))
    )
    (net (code "124") (name "PE13_TOGGLE2") (class "Default")
      (node (ref "S2") (pin "1") (pinfunction "O_1") (pintype "passive"))
      (node (ref "U$9") (pin "44") (pinfunction "PE13/TIM1_CH3(5T)_44") (pintype "bidirectional"))
    )
    (net (code "125") (name "PE14_TOGGLE3") (class "Default")
      (node (ref "S3") (pin "1") (pinfunction "O_1") (pintype "passive"))
      (node (ref "U$9") (pin "45") (pinfunction "PE14/TIM1_CH4(5T)_45") (pintype "bidirectional"))
    )
    (net (code "126") (name "PE15_TOGGLE4") (class "Default")
      (node (ref "S4") (pin "1") (pinfunction "O_1") (pintype "passive"))
      (node (ref "U$9") (pin "46") (pinfunction "PE15/TIM1_BKIN(5T)_46") (pintype "bidirectional"))
    )
    (net (code "127") (name "RESET") (class "Default")
      (node (ref "AQM0802A-RN-GBW") (pin "P$9") (pinfunction "XRSETB_P$9") (pintype "bidirectional"))
      (node (ref "R2") (pin "1") (pinfunction "1_1") (pintype "passive"))
      (node (ref "S9") (pin "3") (pinfunction "P_3") (pintype "passive"))
      (node (ref "S9") (pin "4") (pinfunction "P1_4") (pintype "passive"))
      (node (ref "SJ5") (pin "2") (pinfunction "2_2") (pintype "passive"))
      (node (ref "U$9") (pin "14") (pinfunction "NRST_14") (pintype "bidirectional"))
    )
    (net (code "128") (name "unconnected-(AQM0802A-RN-GBW-VO-PadP$1)") (class "Default")
      (node (ref "AQM0802A-RN-GBW") (pin "P$1") (pinfunction "VO_P$1") (pintype "bidirectional"))
    )
    (net (code "129") (name "unconnected-(IC3-CBUS0-Pad23)") (class "Default")
      (node (ref "IC3") (pin "23") (pinfunction "CBUS0_23") (pintype "bidirectional"))
    )
    (net (code "130") (name "unconnected-(IC3-CBUS1-Pad22)") (class "Default")
      (node (ref "IC3") (pin "22") (pinfunction "CBUS1_22") (pintype "bidirectional"))
    )
    (net (code "131") (name "unconnected-(IC3-CBUS2-Pad13)") (class "Default")
      (node (ref "IC3") (pin "13") (pinfunction "CBUS2_13") (pintype "bidirectional"))
    )
    (net (code "132") (name "unconnected-(IC3-CBUS3-Pad14)") (class "Default")
      (node (ref "IC3") (pin "14") (pinfunction "CBUS3_14") (pintype "bidirectional"))
    )
    (net (code "133") (name "unconnected-(IC3-CBUS4-Pad12)") (class "Default")
      (node (ref "IC3") (pin "12") (pinfunction "CBUS4_12") (pintype "bidirectional"))
    )
    (net (code "134") (name "unconnected-(IC3-NC-Pad8)") (class "Default")
      (node (ref "IC3") (pin "8") (pinfunction "NC_8") (pintype "no_connect"))
    )
    (net (code "135") (name "unconnected-(IC3-NC-Pad24)") (class "Default")
      (node (ref "IC3") (pin "24") (pinfunction "NC_24") (pintype "no_connect"))
    )
    (net (code "136") (name "unconnected-(IC3-OSCI-Pad27)") (class "Default")
      (node (ref "IC3") (pin "27") (pinfunction "OSCI_27") (pintype "input"))
    )
    (net (code "137") (name "unconnected-(IC3-OSCO-Pad28)") (class "Default")
      (node (ref "IC3") (pin "28") (pinfunction "OSCO_28") (pintype "output"))
    )
    (net (code "138") (name "unconnected-(IC3-_CTS-Pad11)") (class "Default")
      (node (ref "IC3") (pin "11") (pinfunction "_CTS_11") (pintype "input"))
    )
    (net (code "139") (name "unconnected-(IC3-_DCD-Pad10)") (class "Default")
      (node (ref "IC3") (pin "10") (pinfunction "_DCD_10") (pintype "input"))
    )
    (net (code "140") (name "unconnected-(IC3-_DSR-Pad9)") (class "Default")
      (node (ref "IC3") (pin "9") (pinfunction "_DSR_9") (pintype "input"))
    )
    (net (code "141") (name "unconnected-(IC3-_DTR-Pad2)") (class "Default")
      (node (ref "IC3") (pin "2") (pinfunction "_DTR_2") (pintype "input"))
    )
    (net (code "142") (name "unconnected-(IC3-_RESET-Pad19)") (class "Default")
      (node (ref "IC3") (pin "19") (pinfunction "_RESET_19") (pintype "input"))
    )
    (net (code "143") (name "unconnected-(IC3-_RI-Pad6)") (class "Default")
      (node (ref "IC3") (pin "6") (pinfunction "_RI_6") (pintype "input"))
    )
    (net (code "144") (name "unconnected-(IC3-_RTS-Pad3)") (class "Default")
      (node (ref "IC3") (pin "3") (pinfunction "_RTS_3") (pintype "output"))
    )
    (net (code "145") (name "unconnected-(S1-S-Pad3)") (class "Default")
      (node (ref "S1") (pin "3") (pinfunction "S_3") (pintype "passive"))
    )
    (net (code "146") (name "unconnected-(S2-S-Pad3)") (class "Default")
      (node (ref "S2") (pin "3") (pinfunction "S_3") (pintype "passive"))
    )
    (net (code "147") (name "unconnected-(S3-S-Pad3)") (class "Default")
      (node (ref "S3") (pin "3") (pinfunction "S_3") (pintype "passive"))
    )
    (net (code "148") (name "unconnected-(S4-S-Pad3)") (class "Default")
      (node (ref "S4") (pin "3") (pinfunction "S_3") (pintype "passive"))
    )
    (net (code "149") (name "unconnected-(SV1-Pad1)") (class "Default")
      (node (ref "SV1") (pin "1") (pinfunction "1_1") (pintype "passive"))
    )
    (net (code "150") (name "unconnected-(SV1-Pad4)") (class "Default")
      (node (ref "SV1") (pin "4") (pinfunction "4_4") (pintype "passive"))
    )
    (net (code "151") (name "unconnected-(SV1-Pad5)") (class "Default")
      (node (ref "SV1") (pin "5") (pinfunction "5_5") (pintype "passive"))
    )
    (net (code "152") (name "unconnected-(SV1-Pad7)") (class "Default")
      (node (ref "SV1") (pin "7") (pinfunction "7_7") (pintype "passive"))
    )
    (net (code "153") (name "unconnected-(SV1-Pad9)") (class "Default")
      (node (ref "SV1") (pin "9") (pinfunction "9_9") (pintype "passive"))
    )
    (net (code "154") (name "unconnected-(SV1-Pad10)") (class "Default")
      (node (ref "SV1") (pin "10") (pinfunction "10_10") (pintype "passive"))
    )
    (net (code "155") (name "unconnected-(SV2-Pad1)") (class "Default")
      (node (ref "SV2") (pin "1") (pinfunction "1_1") (pintype "passive"))
    )
    (net (code "156") (name "unconnected-(SV2-Pad4)") (class "Default")
      (node (ref "SV2") (pin "4") (pinfunction "4_4") (pintype "passive"))
    )
    (net (code "157") (name "unconnected-(SV2-Pad5)") (class "Default")
      (node (ref "SV2") (pin "5") (pinfunction "5_5") (pintype "passive"))
    )
    (net (code "158") (name "unconnected-(SV2-Pad7)") (class "Default")
      (node (ref "SV2") (pin "7") (pinfunction "7_7") (pintype "passive"))
    )
    (net (code "159") (name "unconnected-(SV2-Pad9)") (class "Default")
      (node (ref "SV2") (pin "9") (pinfunction "9_9") (pintype "passive"))
    )
    (net (code "160") (name "unconnected-(SV2-Pad10)") (class "Default")
      (node (ref "SV2") (pin "10") (pinfunction "10_10") (pintype "passive"))
    )
    (net (code "161") (name "unconnected-(SV3-Pad1)") (class "Default")
      (node (ref "SV3") (pin "1") (pinfunction "1_1") (pintype "passive"))
    )
    (net (code "162") (name "unconnected-(SV3-Pad4)") (class "Default")
      (node (ref "SV3") (pin "4") (pinfunction "4_4") (pintype "passive"))
    )
    (net (code "163") (name "unconnected-(SV3-Pad5)") (class "Default")
      (node (ref "SV3") (pin "5") (pinfunction "5_5") (pintype "passive"))
    )
    (net (code "164") (name "unconnected-(SV3-Pad7)") (class "Default")
      (node (ref "SV3") (pin "7") (pinfunction "7_7") (pintype "passive"))
    )
    (net (code "165") (name "unconnected-(SV3-Pad9)") (class "Default")
      (node (ref "SV3") (pin "9") (pinfunction "9_9") (pintype "passive"))
    )
    (net (code "166") (name "unconnected-(SV3-Pad10)") (class "Default")
      (node (ref "SV3") (pin "10") (pinfunction "10_10") (pintype "passive"))
    )
    (net (code "167") (name "unconnected-(SV4-Pad1)") (class "Default")
      (node (ref "SV4") (pin "1") (pinfunction "1_1") (pintype "passive"))
    )
    (net (code "168") (name "unconnected-(SV4-Pad4)") (class "Default")
      (node (ref "SV4") (pin "4") (pinfunction "4_4") (pintype "passive"))
    )
    (net (code "169") (name "unconnected-(SV4-Pad5)") (class "Default")
      (node (ref "SV4") (pin "5") (pinfunction "5_5") (pintype "passive"))
    )
    (net (code "170") (name "unconnected-(SV4-Pad7)") (class "Default")
      (node (ref "SV4") (pin "7") (pinfunction "7_7") (pintype "passive"))
    )
    (net (code "171") (name "unconnected-(SV4-Pad9)") (class "Default")
      (node (ref "SV4") (pin "9") (pinfunction "9_9") (pintype "passive"))
    )
    (net (code "172") (name "unconnected-(SV4-Pad10)") (class "Default")
      (node (ref "SV4") (pin "10") (pinfunction "10_10") (pintype "passive"))
    )
    (net (code "173") (name "unconnected-(U$1-PadCD1)") (class "Default")
      (node (ref "U$1") (pin "CD1") (pinfunction "CD1_CD1") (pintype "bidirectional"))
    )
    (net (code "174") (name "unconnected-(U$1-PadCD2)") (class "Default")
      (node (ref "U$1") (pin "CD2") (pinfunction "CD2_CD2") (pintype "bidirectional"))
    )
    (net (code "175") (name "unconnected-(U$8A-VREF-Pad5)") (class "Default")
      (node (ref "U$8") (pin "5") (pinfunction "VREF_5") (pintype "bidirectional"))
    )
    (net (code "176") (name "unconnected-(U$9-PA8{slash}MCO1(5T)-Pad67)") (class "Default")
      (node (ref "U$9") (pin "67") (pinfunction "PA8/MCO1(5T)_67") (pintype "bidirectional"))
    )
    (net (code "177") (name "unconnected-(U$9-PC0{slash}ADC123_IN10(5T)-Pad15)") (class "Default")
      (node (ref "U$9") (pin "15") (pinfunction "PC0/ADC123_IN10(5T)_15") (pintype "bidirectional"))
    )
    (net (code "178") (name "unconnected-(U$9-PC1{slash}ETH_MDC{slash}ADC123_IN11(5T)-Pad16)") (class "Default")
      (node (ref "U$9") (pin "16") (pinfunction "PC1/ETH_MDC/ADC123_IN11(5T)_16") (pintype "bidirectional"))
    )
    (net (code "179") (name "unconnected-(U$9-PC2{slash}ETH_MII_TXD2{slash}ADC123_IN12(5T)-Pad17)") (class "Default")
      (node (ref "U$9") (pin "17") (pinfunction "PC2/ETH_MII_TXD2/ADC123_IN12(5T)_17") (pintype "bidirectional"))
    )
    (net (code "180") (name "unconnected-(U$9-PC3{slash}ETH_MII_TX_CLK{slash}ADC123_IN13(5T)-Pad18)") (class "Default")
      (node (ref "U$9") (pin "18") (pinfunction "PC3/ETH_MII_TX_CLK/ADC123_IN13(5T)_18") (pintype "bidirectional"))
    )
    (net (code "181") (name "unconnected-(U$9-PC4{slash}ETH_MII_RXD0{slash}ADC12_IN14(5T)-Pad33)") (class "Default")
      (node (ref "U$9") (pin "33") (pinfunction "PC4/ETH_MII_RXD0/ADC12_IN14(5T)_33") (pintype "bidirectional"))
    )
    (net (code "182") (name "unconnected-(U$9-PC5{slash}ETH_MII_RXD1{slash}ADC12_IN15(5T)-Pad34)") (class "Default")
      (node (ref "U$9") (pin "34") (pinfunction "PC5/ETH_MII_RXD1/ADC12_IN15(5T)_34") (pintype "bidirectional"))
    )
    (net (code "183") (name "unconnected-(U$9-PC14{slash}OSC32_IN(5T)-Pad8)") (class "Default")
      (node (ref "U$9") (pin "8") (pinfunction "PC14/OSC32_IN(5T)_8") (pintype "bidirectional"))
    )
    (net (code "184") (name "unconnected-(U$9-PC15{slash}OSC32_OUT(5T)-Pad9)") (class "Default")
      (node (ref "U$9") (pin "9") (pinfunction "PC15/OSC32_OUT(5T)_9") (pintype "bidirectional"))
    )
    (net (code "185") (name "unconnected-(U$9-PD7(5T)-Pad88)") (class "Default")
      (node (ref "U$9") (pin "88") (pinfunction "PD7(5T)_88") (pintype "bidirectional"))
    )
    (net (code "186") (name "unconnected-(U$9-PE6{slash}TIM9_CH2(5T)-Pad5)") (class "Default")
      (node (ref "U$9") (pin "5") (pinfunction "PE6/TIM9_CH2(5T)_5") (pintype "bidirectional"))
    )
    (net (code "187") (name "unconnected-(U$9-PE10{slash}TIM1_CH2N(5T)-Pad41)") (class "Default")
      (node (ref "U$9") (pin "41") (pinfunction "PE10/TIM1_CH2N(5T)_41") (pintype "bidirectional"))
    )
    (net (code "188") (name "unconnected-(U$9-VBAT-Pad6)") (class "Default")
      (node (ref "U$9") (pin "6") (pinfunction "VBAT_6") (pintype "bidirectional"))
    )
    (net (code "189") (name "unconnected-(U$9-VREF+-Pad21)") (class "Default")
      (node (ref "U$9") (pin "21") (pinfunction "VREF+_21") (pintype "bidirectional"))
    )
    (net (code "190") (name "unconnected-(U$10-ES_CL-Pad6)") (class "Default")
      (node (ref "U$10") (pin "6") (pinfunction "ES_CL_6") (pintype "bidirectional"))
    )
    (net (code "191") (name "unconnected-(U$10-ES_DA-Pad5)") (class "Default")
      (node (ref "U$10") (pin "5") (pinfunction "ES_DA_5") (pintype "bidirectional"))
    )
    (net (code "192") (name "unconnected-(U$10-FSYNC-Pad7)") (class "Default")
      (node (ref "U$10") (pin "7") (pinfunction "FSYNC_7") (pintype "bidirectional"))
    )
    (net (code "193") (name "unconnected-(U$12C-O-Pad2)") (class "Default")
      (node (ref "U$12") (pin "2") (pinfunction "O_2") (pintype "output"))
    )
    (net (code "194") (name "unconnected-(U$13-NC-Pad8)") (class "Default")
      (node (ref "U$13") (pin "8") (pinfunction "NC_8") (pintype "bidirectional"))
    )
    (net (code "195") (name "unconnected-(U$13-NC{slash}2-Pad11)") (class "Default")
      (node (ref "U$13") (pin "11") (pinfunction "NC/2_11") (pintype "bidirectional"))
    )
    (net (code "196") (name "unconnected-(U$13-NC{slash}3-Pad12)") (class "Default")
      (node (ref "U$13") (pin "12") (pinfunction "NC/3_12") (pintype "bidirectional"))
    )
    (net (code "197") (name "unconnected-(U$13-PGOOD-Pad10)") (class "Default")
      (node (ref "U$13") (pin "10") (pinfunction "PGOOD_10") (pintype "bidirectional"))
    )
    (net (code "198") (name "unconnected-(U$13-SEQ-Pad9)") (class "Default")
      (node (ref "U$13") (pin "9") (pinfunction "SEQ_9") (pintype "bidirectional"))
    )
    (net (code "199") (name "unconnected-(X1-Pad4)") (class "Default")
      (node (ref "X1") (pin "4") (pinfunction "4_4") (pintype "input"))
    )
    (net (code "200") (name "unconnected-(X2-Pad3)") (class "Default")
      (node (ref "X2") (pin "3") (pinfunction "3_3") (pintype "passive"))
    )
    (net (code "201") (name "unconnected-(X3-Pad3)") (class "Default")
      (node (ref "X3") (pin "3") (pinfunction "3_3") (pintype "passive"))
    )
    (net (code "202") (name "unconnected-(X3-Pad5)") (class "Default")
      (node (ref "X3") (pin "5") (pinfunction "5_5") (pintype "passive"))
    )
    (net (code "203") (name "unconnected-(X3-Pad6)") (class "Default")
      (node (ref "X3") (pin "6") (pinfunction "6_6") (pintype "passive"))
    )
    (net (code "204") (name "unconnected-(X3-S-PadP$11)") (class "Default")
      (node (ref "X3") (pin "P$11") (pinfunction "S_P$11") (pintype "passive"))
    )
    (net (code "205") (name "unconnected-(X3-S-PadP$12)") (class "Default")
      (node (ref "X3") (pin "P$12") (pinfunction "S_P$12") (pintype "passive"))
    )
    (net (code "206") (name "unconnected-(XB1-AD0{slash}DIO0-Pad20)") (class "Default")
      (node (ref "XB1") (pin "20") (pinfunction "AD0/DIO0_20") (pintype "bidirectional"))
    )
    (net (code "207") (name "unconnected-(XB1-AD1{slash}DIO1-Pad19)") (class "Default")
      (node (ref "XB1") (pin "19") (pinfunction "AD1/DIO1_19") (pintype "bidirectional"))
    )
    (net (code "208") (name "unconnected-(XB1-AD2{slash}DIO2-Pad18)") (class "Default")
      (node (ref "XB1") (pin "18") (pinfunction "AD2/DIO2_18") (pintype "bidirectional"))
    )
    (net (code "209") (name "unconnected-(XB1-ASSOC{slash}AD5{slash}DIO5-Pad15)") (class "Default")
      (node (ref "XB1") (pin "15") (pinfunction "ASSOC/AD5/DIO5_15") (pintype "bidirectional"))
    )
    (net (code "210") (name "unconnected-(XB1-CD{slash}DOUT_EN{slash}DO8-Pad4)") (class "Default")
      (node (ref "XB1") (pin "4") (pinfunction "CD/DOUT_EN/DO8_4") (pintype "output"))
    )
    (net (code "211") (name "unconnected-(XB1-COORD_SEL{slash}AD3{slash}DIO3-Pad17)") (class "Default")
      (node (ref "XB1") (pin "17") (pinfunction "COORD_SEL/AD3/DIO3_17") (pintype "bidirectional"))
    )
    (net (code "212") (name "unconnected-(XB1-ON{slash}~{SLEEP}-Pad13)") (class "Default")
      (node (ref "XB1") (pin "13") (pinfunction "ON/~{SLEEP}_13") (pintype "output"))
    )
    (net (code "213") (name "unconnected-(XB1-PWM0{slash}RSSI-Pad6)") (class "Default")
      (node (ref "XB1") (pin "6") (pinfunction "PWM0/RSSI_6") (pintype "output"))
    )
    (net (code "214") (name "unconnected-(XB1-RF_TX{slash}AD4{slash}DIO4-Pad11)") (class "Default")
      (node (ref "XB1") (pin "11") (pinfunction "RF_TX/AD4/DIO4_11") (pintype "bidirectional"))
    )
    (net (code "215") (name "unconnected-(XB1-VREF-Pad14)") (class "Default")
      (node (ref "XB1") (pin "14") (pinfunction "VREF_14") (pintype "input"))
    )
    (net (code "216") (name "unconnected-(XB1-~{CTS}{slash}DIO7-Pad12)") (class "Default")
      (node (ref "XB1") (pin "12") (pinfunction "~{CTS}/DIO7_12") (pintype "bidirectional"))
    )
    (net (code "217") (name "unconnected-(XB1-~{DTR}{slash}SLEEP_RQ{slash}DI8-Pad9)") (class "Default")
      (node (ref "XB1") (pin "9") (pinfunction "~{DTR}/SLEEP_RQ/DI8_9") (pintype "bidirectional"))
    )
    (net (code "218") (name "unconnected-(XB1-~{RESET}-Pad5)") (class "Default")
      (node (ref "XB1") (pin "5") (pinfunction "~{RESET}_5") (pintype "input"))
    )
    (net (code "219") (name "unconnected-(XB1-~{RTS}{slash}AD6{slash}DIO6-Pad16)") (class "Default")
      (node (ref "XB1") (pin "16") (pinfunction "~{RTS}/AD6/DIO6_16") (pintype "bidirectional"))
    )
  )
)
